# dabstick_eval_rev00.net
KiCad netlist of a schematic drawn in EAGLE
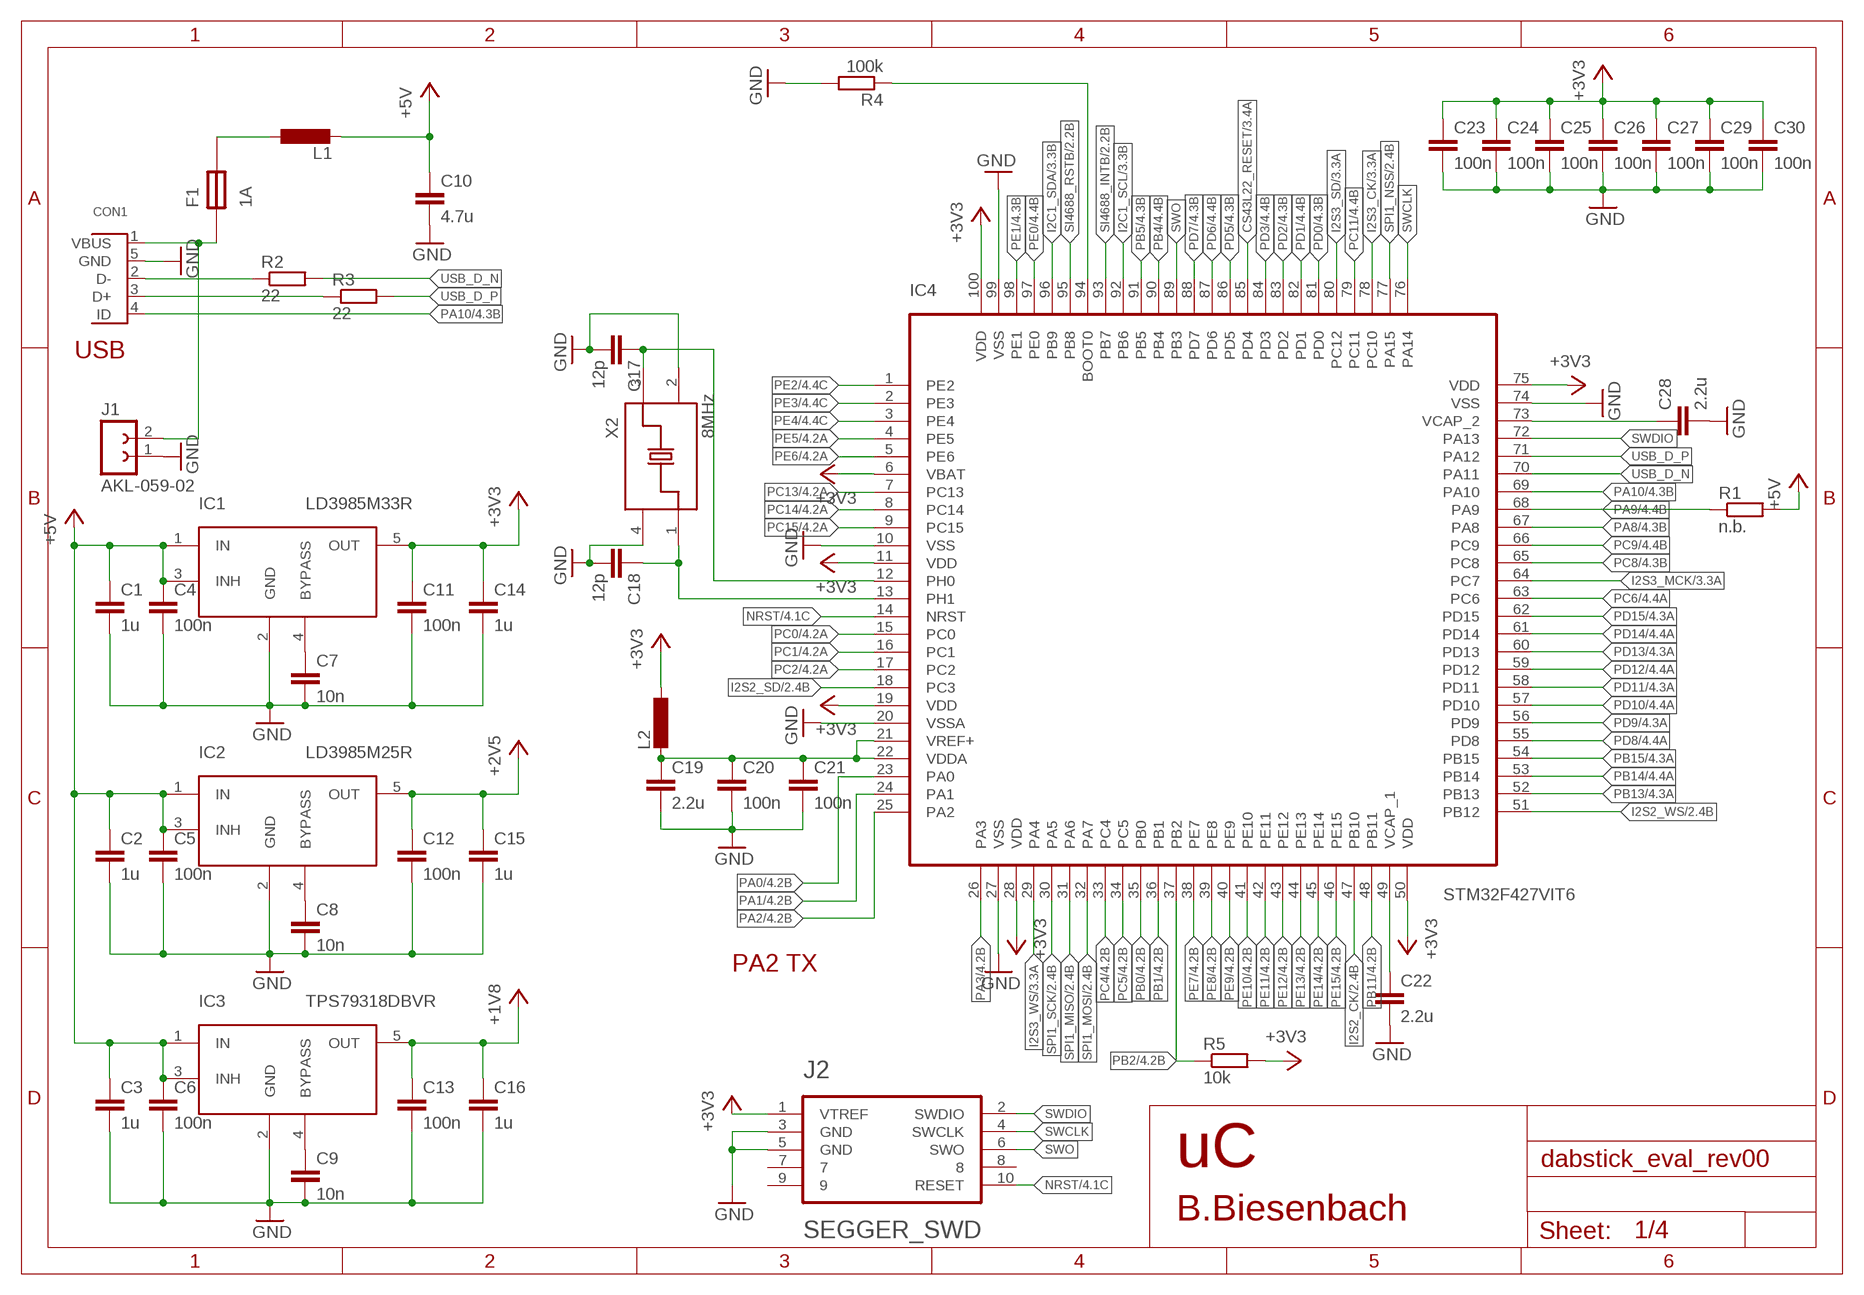
[diagram p0: schematic, sheet 1]
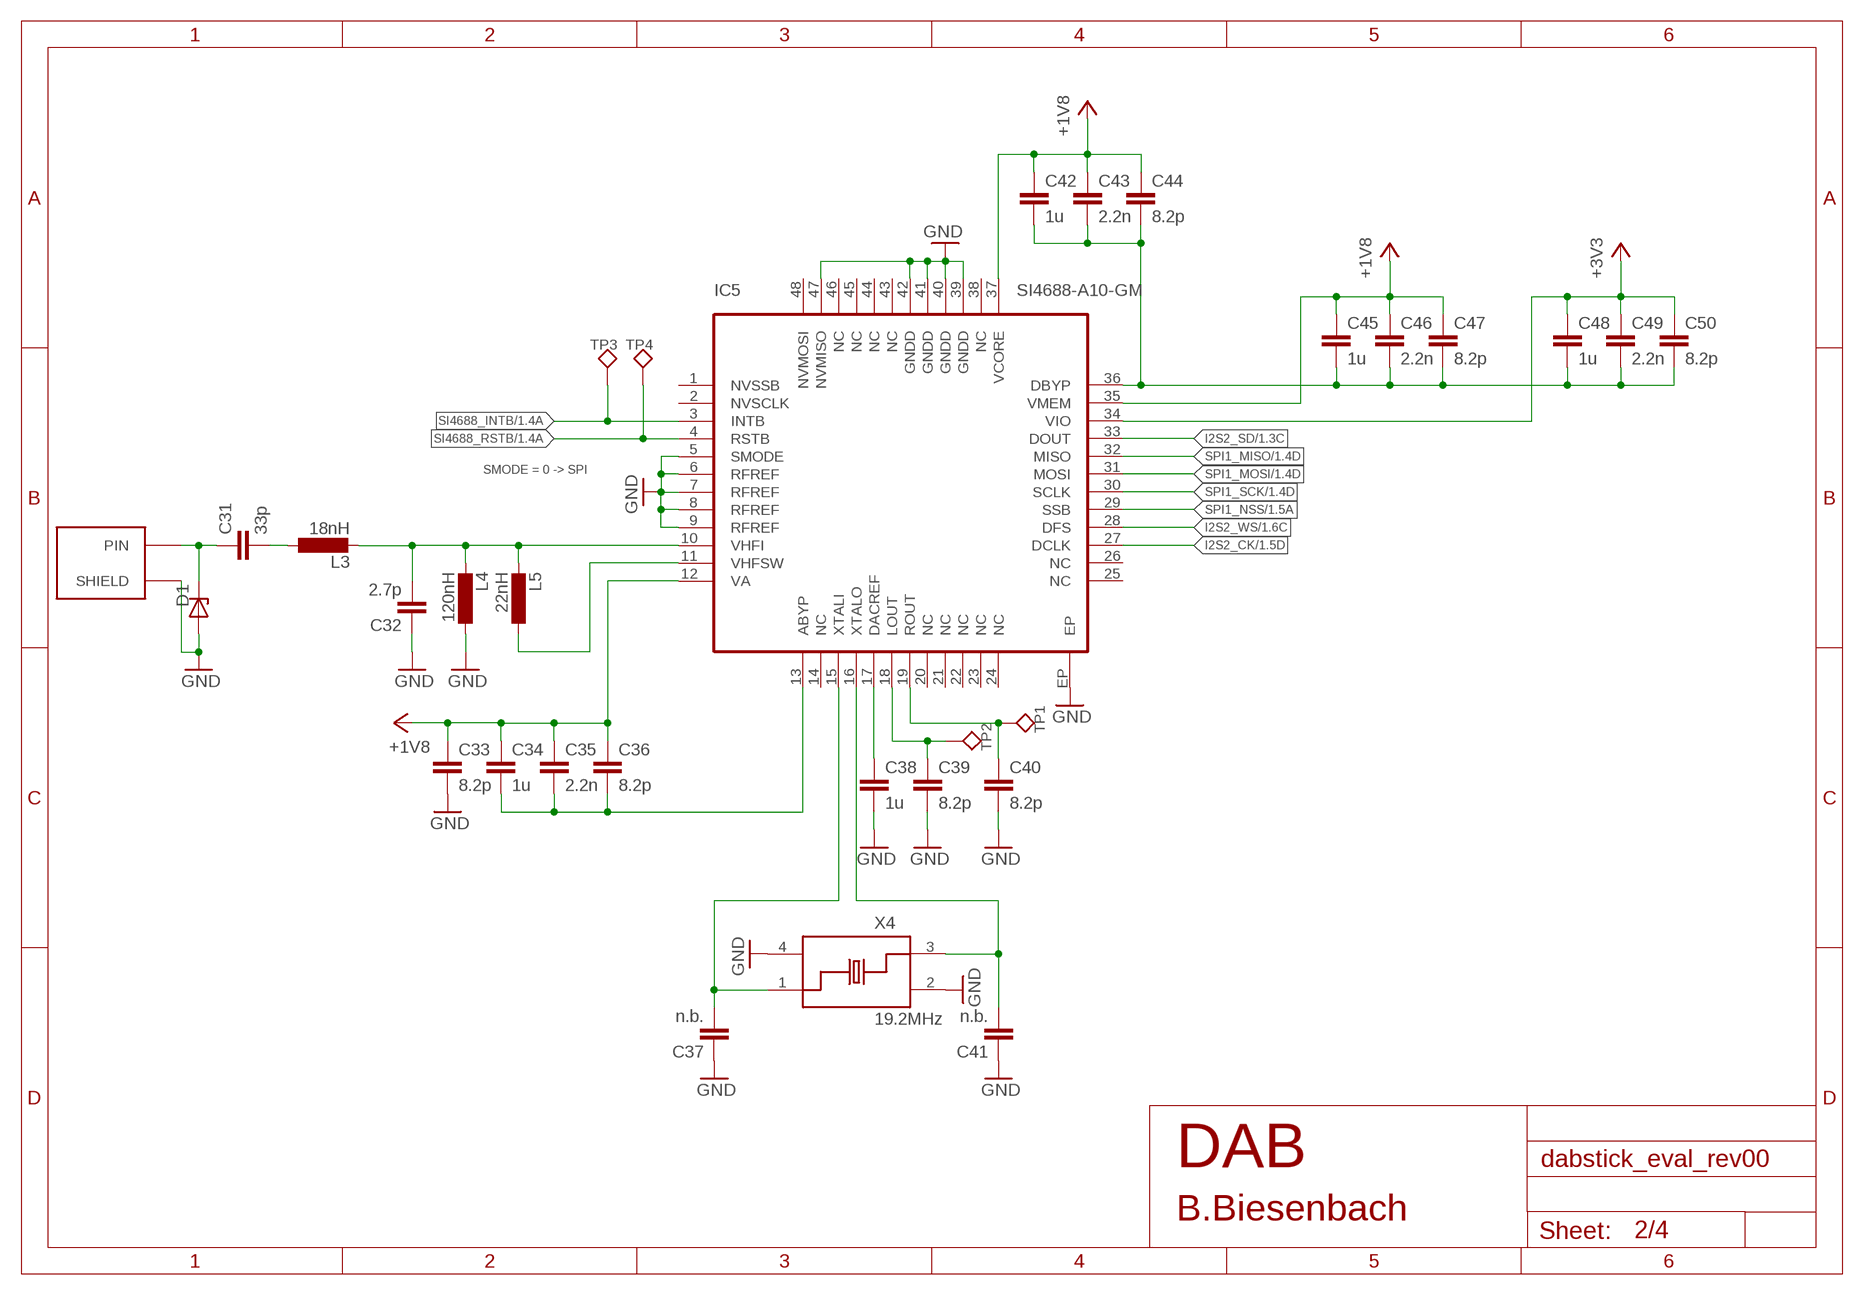
[diagram p1: schematic, sheet 2]
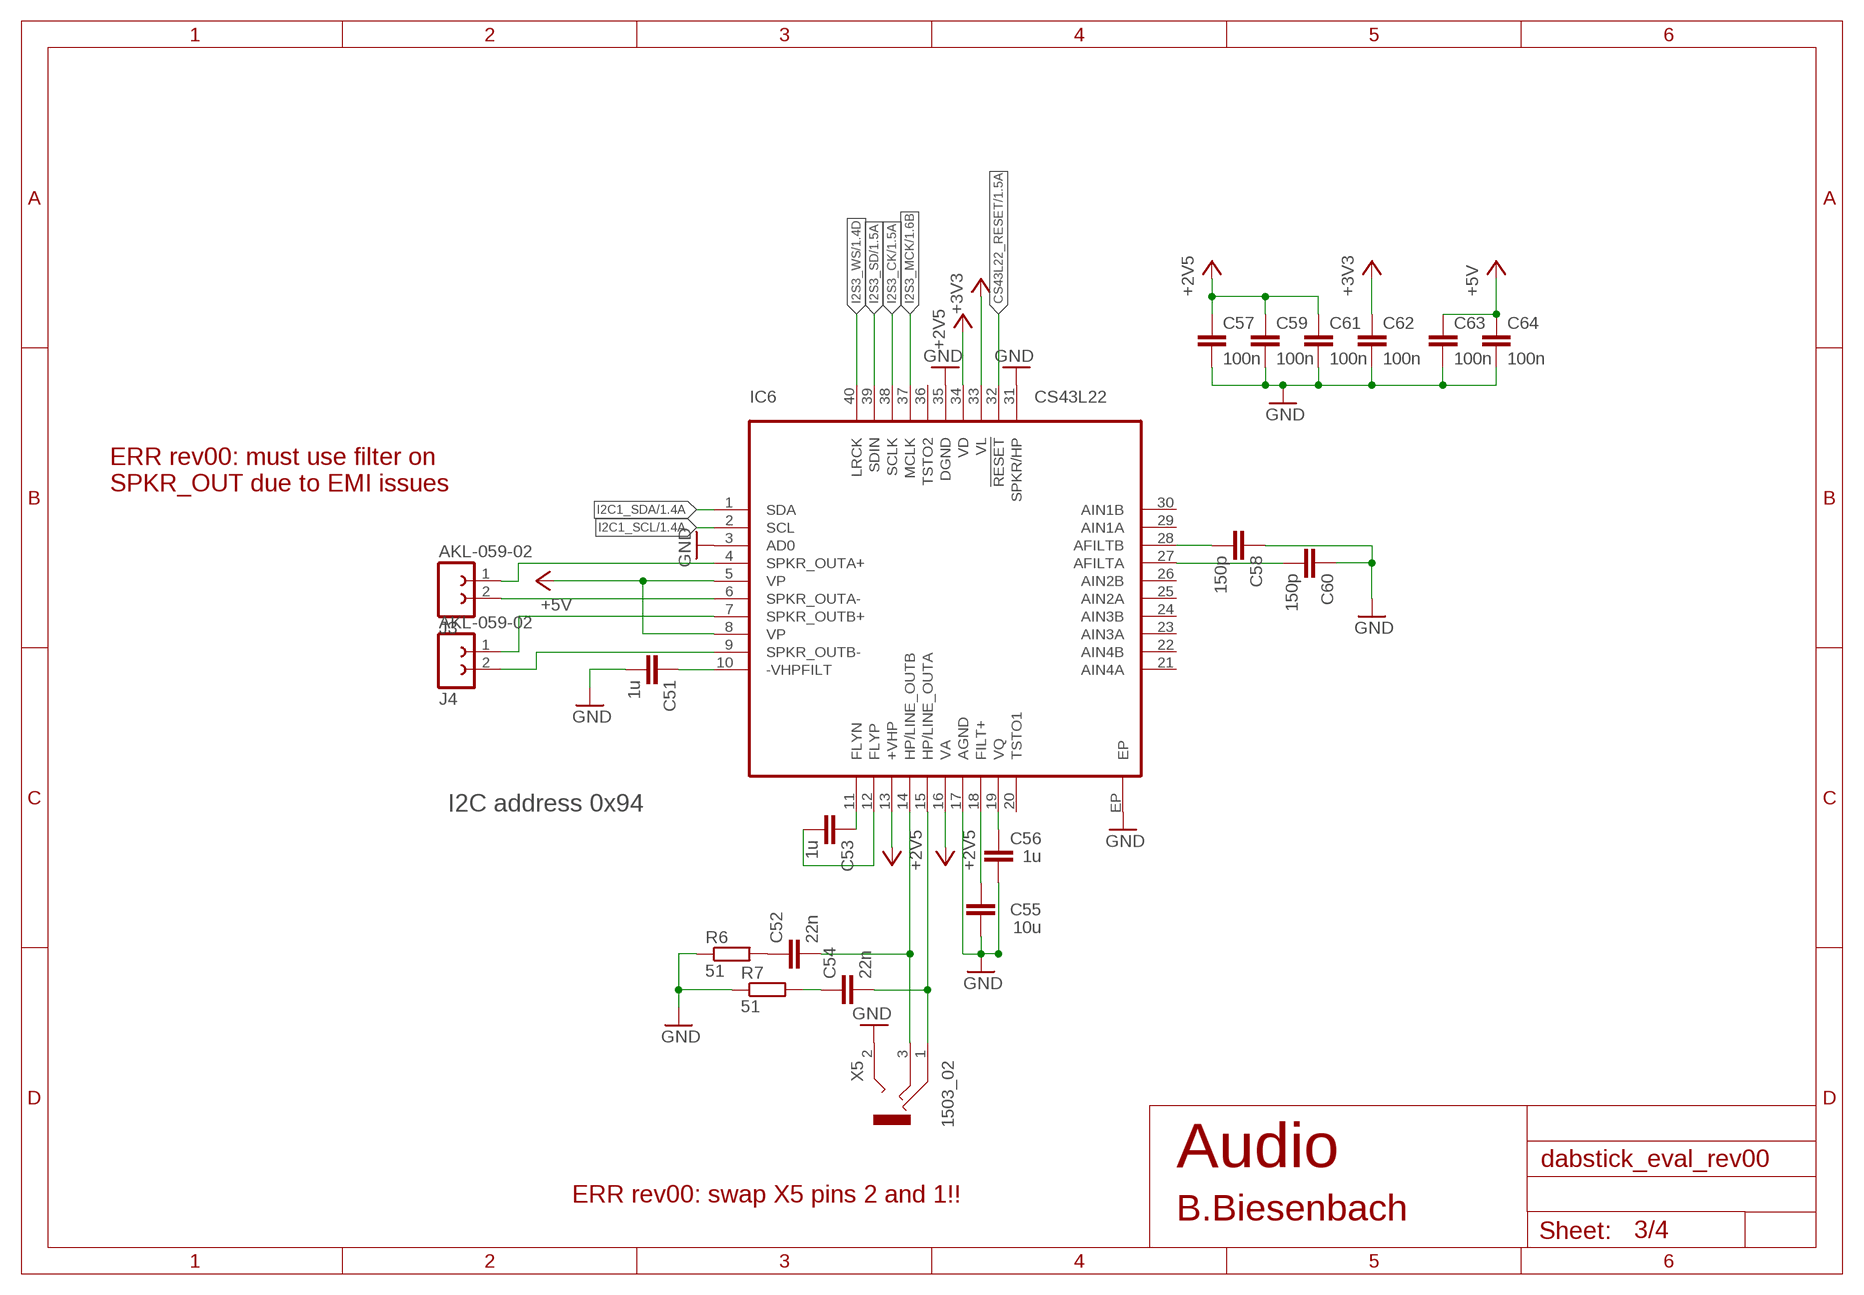
[diagram p2: schematic, sheet 3]
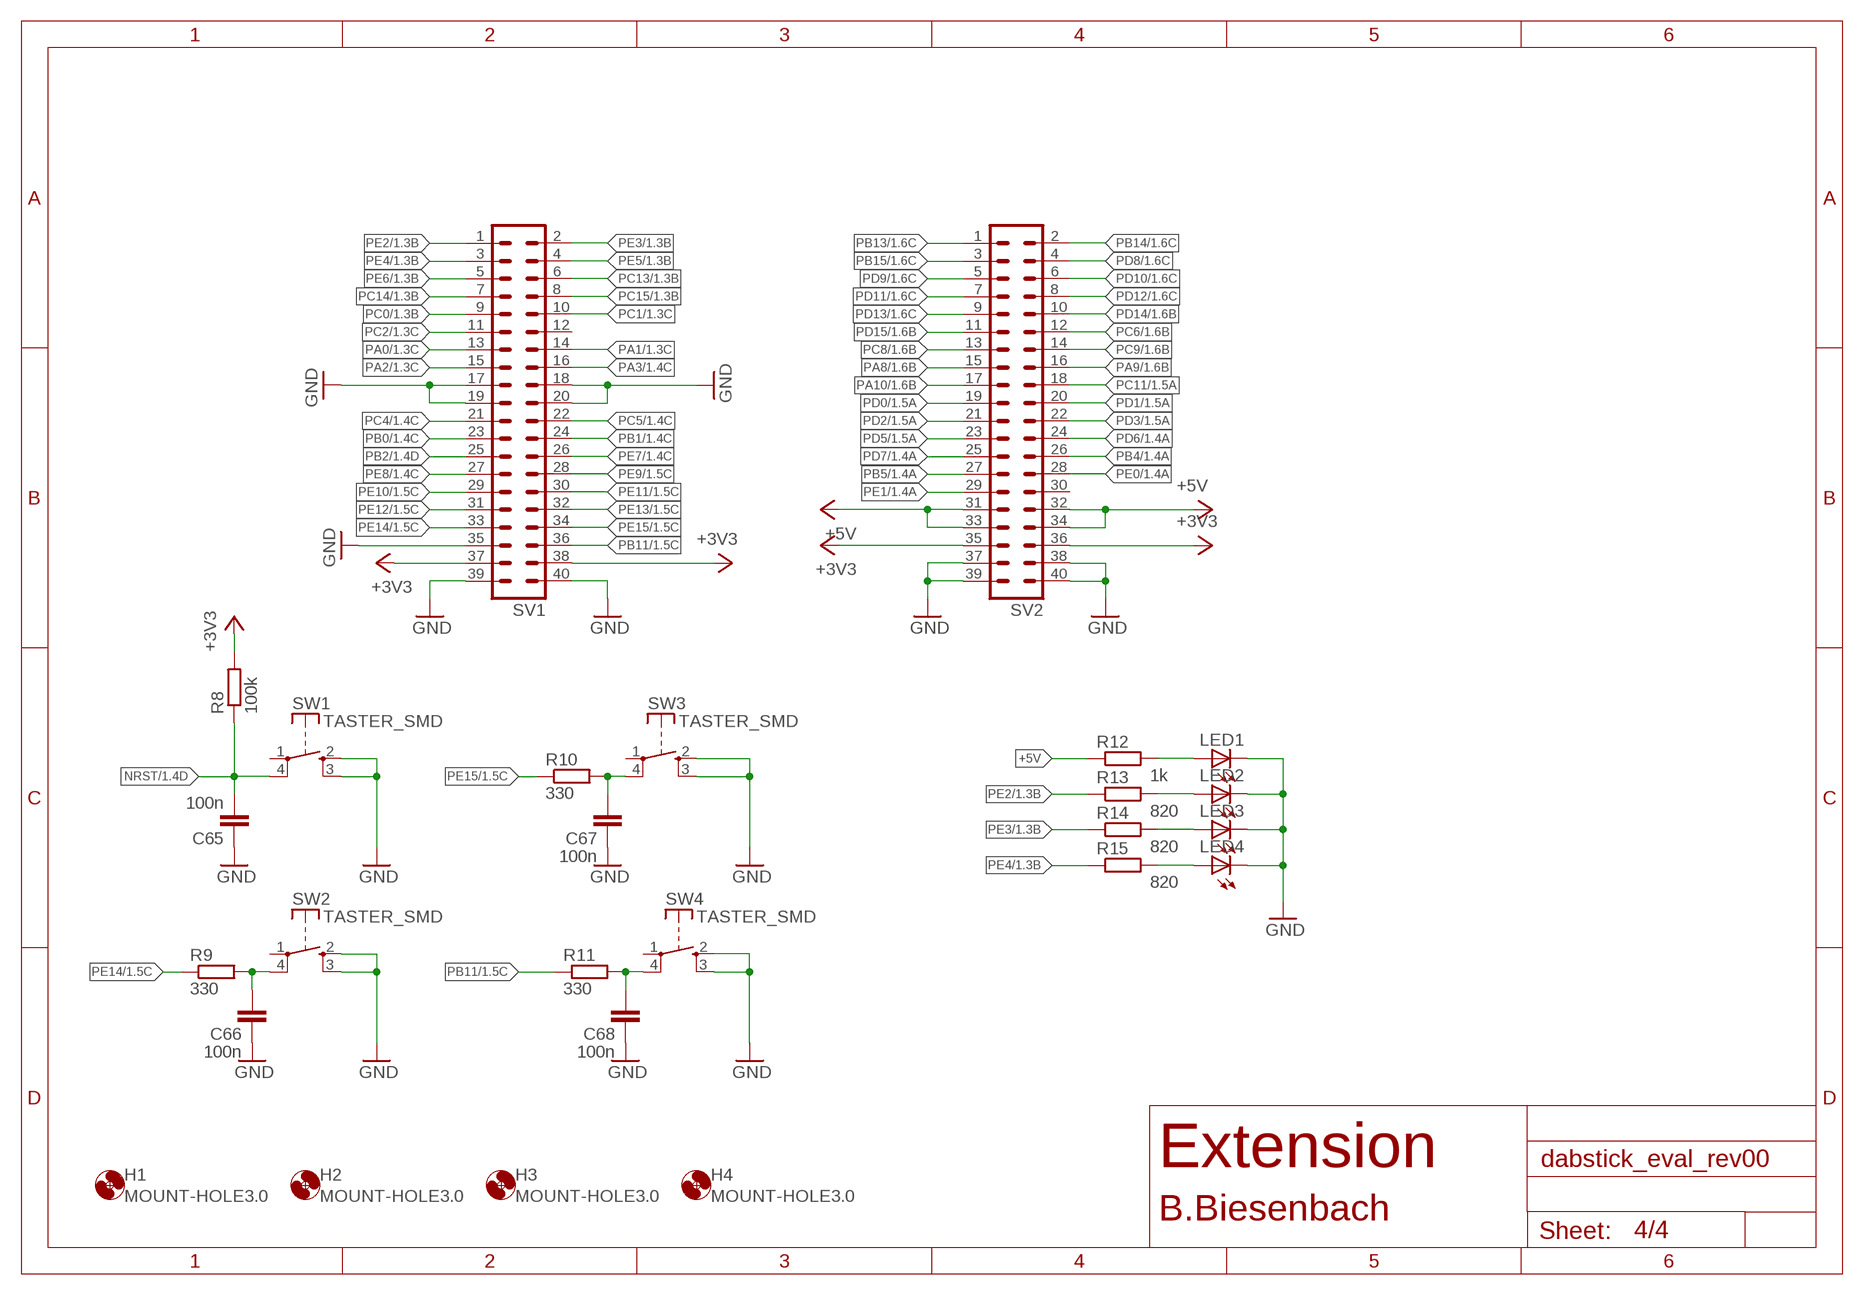
[diagram p3: schematic, sheet 4]

(export (version "E")
  (design (tool "Eeschema 10.0.6"))
  (components
    (comp (ref "C65")
      (value "100n")
      (footprint "eagle-import:SMD0603")
      (libsource (lib "eagle-import") (part "C0603"))
    )
    (comp (ref "C66")
      (value "100n")
      (footprint "eagle-import:SMD0603")
      (libsource (lib "eagle-import") (part "C0603"))
    )
    (comp (ref "C67")
      (value "100n")
      (footprint "eagle-import:SMD0603")
      (libsource (lib "eagle-import") (part "C0603"))
    )
    (comp (ref "C68")
      (value "100n")
      (footprint "eagle-import:SMD0603")
      (libsource (lib "eagle-import") (part "C0603"))
    )
    (comp (ref "H1")
      (value "MOUNT-HOLE3.0")
      (footprint "eagle-import:3,0")
      (libsource (lib "eagle-import") (part "MOUNT-HOLE3.0"))
    )
    (comp (ref "H2")
      (value "MOUNT-HOLE3.0")
      (footprint "eagle-import:3,0")
      (libsource (lib "eagle-import") (part "MOUNT-HOLE3.0"))
    )
    (comp (ref "H3")
      (value "MOUNT-HOLE3.0")
      (footprint "eagle-import:3,0")
      (libsource (lib "eagle-import") (part "MOUNT-HOLE3.0"))
    )
    (comp (ref "H4")
      (value "MOUNT-HOLE3.0")
      (footprint "eagle-import:3,0")
      (libsource (lib "eagle-import") (part "MOUNT-HOLE3.0"))
    )
    (comp (ref "LED1")
      (value "LEDCHIPLED_0603")
      (footprint "eagle-import:CHIPLED_0603")
      (libsource (lib "eagle-import") (part "LEDCHIPLED_0603"))
    )
    (comp (ref "LED2")
      (value "LEDCHIPLED_0603")
      (footprint "eagle-import:CHIPLED_0603")
      (libsource (lib "eagle-import") (part "LEDCHIPLED_0603"))
    )
    (comp (ref "LED3")
      (value "LEDCHIPLED_0603")
      (footprint "eagle-import:CHIPLED_0603")
      (libsource (lib "eagle-import") (part "LEDCHIPLED_0603"))
    )
    (comp (ref "LED4")
      (value "LEDCHIPLED_0603")
      (footprint "eagle-import:CHIPLED_0603")
      (libsource (lib "eagle-import") (part "LEDCHIPLED_0603"))
    )
    (comp (ref "R8")
      (value "100k")
      (footprint "eagle-import:SMD0603")
      (libsource (lib "eagle-import") (part "R0603"))
    )
    (comp (ref "R9")
      (value "330")
      (footprint "eagle-import:SMD0603")
      (libsource (lib "eagle-import") (part "R0603"))
    )
    (comp (ref "R10")
      (value "330")
      (footprint "eagle-import:SMD0603")
      (libsource (lib "eagle-import") (part "R0603"))
    )
    (comp (ref "R11")
      (value "330")
      (footprint "eagle-import:SMD0603")
      (libsource (lib "eagle-import") (part "R0603"))
    )
    (comp (ref "R12")
      (value "1k")
      (footprint "eagle-import:SMD0603")
      (libsource (lib "eagle-import") (part "R0603"))
    )
    (comp (ref "R13")
      (value "820")
      (footprint "eagle-import:SMD0603")
      (libsource (lib "eagle-import") (part "R0603"))
    )
    (comp (ref "R14")
      (value "820")
      (footprint "eagle-import:SMD0603")
      (libsource (lib "eagle-import") (part "R0603"))
    )
    (comp (ref "R15")
      (value "820")
      (footprint "eagle-import:SMD0603")
      (libsource (lib "eagle-import") (part "R0603"))
    )
    (comp (ref "SV1")
      (value "MA20-2")
      (footprint "eagle-import:MA20-2")
      (libsource (lib "eagle-import") (part "MA20-2"))
    )
    (comp (ref "SV2")
      (value "MA20-2")
      (footprint "eagle-import:MA20-2")
      (libsource (lib "eagle-import") (part "MA20-2"))
    )
    (comp (ref "SW1")
      (value "TASTER_SMD")
      (footprint "eagle-import:TASTER_SMD_ALPS")
      (libsource (lib "eagle-import") (part "TASTER_SMD"))
    )
    (comp (ref "SW2")
      (value "TASTER_SMD")
      (footprint "eagle-import:TASTER_SMD_ALPS")
      (libsource (lib "eagle-import") (part "TASTER_SMD"))
    )
    (comp (ref "SW3")
      (value "TASTER_SMD")
      (footprint "eagle-import:TASTER_SMD_ALPS")
      (libsource (lib "eagle-import") (part "TASTER_SMD"))
    )
    (comp (ref "SW4")
      (value "TASTER_SMD")
      (footprint "eagle-import:TASTER_SMD_ALPS")
      (libsource (lib "eagle-import") (part "TASTER_SMD"))
    )
    (comp (ref "C1")
      (value "1u")
      (footprint "eagle-import:SMD0603")
      (libsource (lib "eagle-import") (part "C0603"))
    )
    (comp (ref "C2")
      (value "1u")
      (footprint "eagle-import:SMD0603")
      (libsource (lib "eagle-import") (part "C0603"))
    )
    (comp (ref "C3")
      (value "1u")
      (footprint "eagle-import:SMD0603")
      (libsource (lib "eagle-import") (part "C0603"))
    )
    (comp (ref "C4")
      (value "100n")
      (footprint "eagle-import:SMD0603")
      (libsource (lib "eagle-import") (part "C0603"))
    )
    (comp (ref "C5")
      (value "100n")
      (footprint "eagle-import:SMD0603")
      (libsource (lib "eagle-import") (part "C0603"))
    )
    (comp (ref "C6")
      (value "100n")
      (footprint "eagle-import:SMD0603")
      (libsource (lib "eagle-import") (part "C0603"))
    )
    (comp (ref "C7")
      (value "10n")
      (footprint "eagle-import:SMD0603")
      (libsource (lib "eagle-import") (part "C0603"))
    )
    (comp (ref "C8")
      (value "10n")
      (footprint "eagle-import:SMD0603")
      (libsource (lib "eagle-import") (part "C0603"))
    )
    (comp (ref "C9")
      (value "10n")
      (footprint "eagle-import:SMD0603")
      (libsource (lib "eagle-import") (part "C0603"))
    )
    (comp (ref "C10")
      (value "4.7u")
      (footprint "eagle-import:0805")
      (libsource (lib "eagle-import") (part "C0805"))
    )
    (comp (ref "C11")
      (value "100n")
      (footprint "eagle-import:SMD0603")
      (libsource (lib "eagle-import") (part "C0603"))
    )
    (comp (ref "C12")
      (value "100n")
      (footprint "eagle-import:SMD0603")
      (libsource (lib "eagle-import") (part "C0603"))
    )
    (comp (ref "C13")
      (value "100n")
      (footprint "eagle-import:SMD0603")
      (libsource (lib "eagle-import") (part "C0603"))
    )
    (comp (ref "C14")
      (value "1u")
      (footprint "eagle-import:SMD0603")
      (libsource (lib "eagle-import") (part "C0603"))
    )
    (comp (ref "C15")
      (value "1u")
      (footprint "eagle-import:SMD0603")
      (libsource (lib "eagle-import") (part "C0603"))
    )
    (comp (ref "C16")
      (value "1u")
      (footprint "eagle-import:SMD0603")
      (libsource (lib "eagle-import") (part "C0603"))
    )
    (comp (ref "C17")
      (value "12p")
      (footprint "eagle-import:SMD0603")
      (libsource (lib "eagle-import") (part "C0603"))
    )
    (comp (ref "C18")
      (value "12p")
      (footprint "eagle-import:SMD0603")
      (libsource (lib "eagle-import") (part "C0603"))
    )
    (comp (ref "C19")
      (value "2.2u")
      (footprint "eagle-import:SMD0603")
      (libsource (lib "eagle-import") (part "C0603"))
    )
    (comp (ref "C20")
      (value "100n")
      (footprint "eagle-import:SMD0603")
      (libsource (lib "eagle-import") (part "C0603"))
    )
    (comp (ref "C21")
      (value "100n")
      (footprint "eagle-import:SMD0603")
      (libsource (lib "eagle-import") (part "C0603"))
    )
    (comp (ref "C22")
      (value "2.2u")
      (footprint "eagle-import:SMD0603")
      (libsource (lib "eagle-import") (part "C0603"))
    )
    (comp (ref "C23")
      (value "100n")
      (footprint "eagle-import:SMD0603")
      (libsource (lib "eagle-import") (part "C0603"))
    )
    (comp (ref "C24")
      (value "100n")
      (footprint "eagle-import:SMD0603")
      (libsource (lib "eagle-import") (part "C0603"))
    )
    (comp (ref "C25")
      (value "100n")
      (footprint "eagle-import:SMD0603")
      (libsource (lib "eagle-import") (part "C0603"))
    )
    (comp (ref "C26")
      (value "100n")
      (footprint "eagle-import:SMD0603")
      (libsource (lib "eagle-import") (part "C0603"))
    )
    (comp (ref "C27")
      (value "100n")
      (footprint "eagle-import:SMD0603")
      (libsource (lib "eagle-import") (part "C0603"))
    )
    (comp (ref "C28")
      (value "2.2u")
      (footprint "eagle-import:SMD0603")
      (libsource (lib "eagle-import") (part "C0603"))
    )
    (comp (ref "C29")
      (value "100n")
      (footprint "eagle-import:SMD0603")
      (libsource (lib "eagle-import") (part "C0603"))
    )
    (comp (ref "C30")
      (value "100n")
      (footprint "eagle-import:SMD0603")
      (libsource (lib "eagle-import") (part "C0603"))
    )
    (comp (ref "CON1")
      (value "USB")
      (footprint "eagle-import:USB-B-MICRO-SMT")
      (libsource (lib "eagle-import") (part "USB"))
    )
    (comp (ref "F1")
      (value "1A")
      (footprint "eagle-import:SMD_FUSE")
      (libsource (lib "eagle-import") (part "SMD_FUSE"))
    )
    (comp (ref "IC1")
      (value "LD3985M33R")
      (footprint "eagle-import:SOT23-5")
      (libsource (lib "eagle-import") (part "LD3985M33R"))
    )
    (comp (ref "IC2")
      (value "LD3985M25R")
      (footprint "eagle-import:SOT23-5")
      (libsource (lib "eagle-import") (part "LD3985M25R"))
    )
    (comp (ref "IC3")
      (value "TPS79318DBVR")
      (footprint "eagle-import:SOT23-5")
      (libsource (lib "eagle-import") (part "TPS79318DBVR"))
    )
    (comp (ref "IC4")
      (value "STM32F427VIT6")
      (footprint "eagle-import:LQFP100")
      (libsource (lib "eagle-import") (part "STM32F427VIT6"))
    )
    (comp (ref "J1")
      (value "AKL-059-02")
      (footprint "eagle-import:AKL-059-02")
      (libsource (lib "eagle-import") (part "AKL-059-02"))
    )
    (comp (ref "J2")
      (value "SEGGER_SWD")
      (footprint "eagle-import:HEADER_10_1.27")
      (libsource (lib "eagle-import") (part "SEGGER_SWD"))
    )
    (comp (ref "L1")
      (value "L08050805")
      (footprint "eagle-import:0805")
      (libsource (lib "eagle-import") (part "L08050805"))
    )
    (comp (ref "L2")
      (value "L0603")
      (footprint "eagle-import:SMD0603")
      (libsource (lib "eagle-import") (part "L0603"))
    )
    (comp (ref "R1")
      (value "n.b.")
      (footprint "eagle-import:SMD0603")
      (libsource (lib "eagle-import") (part "R0603"))
    )
    (comp (ref "R2")
      (value "22")
      (footprint "eagle-import:SMD0603")
      (libsource (lib "eagle-import") (part "R0603"))
    )
    (comp (ref "R3")
      (value "22")
      (footprint "eagle-import:SMD0603")
      (libsource (lib "eagle-import") (part "R0603"))
    )
    (comp (ref "R4")
      (value "100k")
      (footprint "eagle-import:SMD0603")
      (libsource (lib "eagle-import") (part "R0603"))
    )
    (comp (ref "R5")
      (value "10k")
      (footprint "eagle-import:SMD0603")
      (libsource (lib "eagle-import") (part "R0603"))
    )
    (comp (ref "X2")
      (value "8MHz")
      (footprint "eagle-import:XTAL_3.2X5")
      (libsource (lib "eagle-import") (part "XTAL_3.2X5"))
    )
    (comp (ref "C31")
      (value "33p")
      (footprint "eagle-import:SMD0402")
      (libsource (lib "eagle-import") (part "C0402"))
    )
    (comp (ref "C32")
      (value "2.7p")
      (footprint "eagle-import:SMD0402")
      (libsource (lib "eagle-import") (part "C0402"))
    )
    (comp (ref "C33")
      (value "8.2p")
      (footprint "eagle-import:SMD0603")
      (libsource (lib "eagle-import") (part "C0603"))
    )
    (comp (ref "C34")
      (value "1u")
      (footprint "eagle-import:SMD0603")
      (libsource (lib "eagle-import") (part "C0603"))
    )
    (comp (ref "C35")
      (value "2.2n")
      (footprint "eagle-import:SMD0603")
      (libsource (lib "eagle-import") (part "C0603"))
    )
    (comp (ref "C36")
      (value "8.2p")
      (footprint "eagle-import:SMD0603")
      (libsource (lib "eagle-import") (part "C0603"))
    )
    (comp (ref "C37")
      (value "n.b.")
      (footprint "eagle-import:SMD0402")
      (libsource (lib "eagle-import") (part "C0402"))
    )
    (comp (ref "C38")
      (value "1u")
      (footprint "eagle-import:SMD0603")
      (libsource (lib "eagle-import") (part "C0603"))
    )
    (comp (ref "C39")
      (value "8.2p")
      (footprint "eagle-import:SMD0603")
      (libsource (lib "eagle-import") (part "C0603"))
    )
    (comp (ref "C40")
      (value "8.2p")
      (footprint "eagle-import:SMD0603")
      (libsource (lib "eagle-import") (part "C0603"))
    )
    (comp (ref "C41")
      (value "n.b.")
      (footprint "eagle-import:SMD0402")
      (libsource (lib "eagle-import") (part "C0402"))
    )
    (comp (ref "C42")
      (value "1u")
      (footprint "eagle-import:SMD0603")
      (libsource (lib "eagle-import") (part "C0603"))
    )
    (comp (ref "C43")
      (value "2.2n")
      (footprint "eagle-import:SMD0603")
      (libsource (lib "eagle-import") (part "C0603"))
    )
    (comp (ref "C44")
      (value "8.2p")
      (footprint "eagle-import:SMD0603")
      (libsource (lib "eagle-import") (part "C0603"))
    )
    (comp (ref "C45")
      (value "1u")
      (footprint "eagle-import:SMD0603")
      (libsource (lib "eagle-import") (part "C0603"))
    )
    (comp (ref "C46")
      (value "2.2n")
      (footprint "eagle-import:SMD0603")
      (libsource (lib "eagle-import") (part "C0603"))
    )
    (comp (ref "C47")
      (value "8.2p")
      (footprint "eagle-import:SMD0603")
      (libsource (lib "eagle-import") (part "C0603"))
    )
    (comp (ref "C48")
      (value "1u")
      (footprint "eagle-import:SMD0603")
      (libsource (lib "eagle-import") (part "C0603"))
    )
    (comp (ref "C49")
      (value "2.2n")
      (footprint "eagle-import:SMD0603")
      (libsource (lib "eagle-import") (part "C0603"))
    )
    (comp (ref "C50")
      (value "8.2p")
      (footprint "eagle-import:SMD0603")
      (libsource (lib "eagle-import") (part "C0603"))
    )
    (comp (ref "D1")
      (value "ESD9L5.0")
      (footprint "eagle-import:SOD923")
      (libsource (lib "eagle-import") (part "ESD9L5.0"))
    )
    (comp (ref "IC5")
      (value "SI4688-A10-GM")
      (footprint "eagle-import:QFN48")
      (libsource (lib "eagle-import") (part "SI4688-A10-GM"))
    )
    (comp (ref "L3")
      (value "18nH")
      (footprint "eagle-import:SMD0402")
      (libsource (lib "eagle-import") (part "L0402"))
    )
    (comp (ref "L4")
      (value "120nH")
      (footprint "eagle-import:SMD0402")
      (libsource (lib "eagle-import") (part "L0402"))
    )
    (comp (ref "L5")
      (value "22nH")
      (footprint "eagle-import:SMD0402")
      (libsource (lib "eagle-import") (part "L0402"))
    )
    (comp (ref "TP1")
      (value "TP-2-MM")
      (footprint "eagle-import:TP-2-MM")
      (libsource (lib "eagle-import") (part "TP-2-MM"))
    )
    (comp (ref "TP2")
      (value "TP-2-MM")
      (footprint "eagle-import:TP-2-MM")
      (libsource (lib "eagle-import") (part "TP-2-MM"))
    )
    (comp (ref "TP3")
      (value "TP-1-MM")
      (footprint "eagle-import:TP-1-MM")
      (libsource (lib "eagle-import") (part "TP-1-MM"))
    )
    (comp (ref "TP4")
      (value "TP-1-MM")
      (footprint "eagle-import:TP-1-MM")
      (libsource (lib "eagle-import") (part "TP-1-MM"))
    )
    (comp (ref "X3")
      (value "SMA_LP_1.57MM")
      (footprint "eagle-import:SMA_LP_1.57MM")
      (libsource (lib "eagle-import") (part "SMA_LP_1.57MM"))
    )
    (comp (ref "X4")
      (value "19.2MHz")
      (footprint "eagle-import:XTAL_3.2X2.5")
      (libsource (lib "eagle-import") (part "XTAL_3.2X2.5"))
    )
    (comp (ref "C51")
      (value "1u")
      (footprint "eagle-import:SMD0603")
      (libsource (lib "eagle-import") (part "C0603"))
    )
    (comp (ref "C52")
      (value "22n")
      (footprint "eagle-import:SMD0603")
      (libsource (lib "eagle-import") (part "C0603"))
    )
    (comp (ref "C53")
      (value "1u")
      (footprint "eagle-import:SMD0603")
      (libsource (lib "eagle-import") (part "C0603"))
    )
    (comp (ref "C54")
      (value "22n")
      (footprint "eagle-import:SMD0603")
      (libsource (lib "eagle-import") (part "C0603"))
    )
    (comp (ref "C55")
      (value "10u")
      (footprint "eagle-import:SMD0603")
      (libsource (lib "eagle-import") (part "C0603"))
    )
    (comp (ref "C56")
      (value "1u")
      (footprint "eagle-import:SMD0603")
      (libsource (lib "eagle-import") (part "C0603"))
    )
    (comp (ref "C57")
      (value "100n")
      (footprint "eagle-import:SMD0603")
      (libsource (lib "eagle-import") (part "C0603"))
    )
    (comp (ref "C58")
      (value "150p")
      (footprint "eagle-import:SMD0603")
      (libsource (lib "eagle-import") (part "C0603"))
    )
    (comp (ref "C59")
      (value "100n")
      (footprint "eagle-import:SMD0603")
      (libsource (lib "eagle-import") (part "C0603"))
    )
    (comp (ref "C60")
      (value "150p")
      (footprint "eagle-import:SMD0603")
      (libsource (lib "eagle-import") (part "C0603"))
    )
    (comp (ref "C61")
      (value "100n")
      (footprint "eagle-import:SMD0603")
      (libsource (lib "eagle-import") (part "C0603"))
    )
    (comp (ref "C62")
      (value "100n")
      (footprint "eagle-import:SMD0603")
      (libsource (lib "eagle-import") (part "C0603"))
    )
    (comp (ref "C63")
      (value "100n")
      (footprint "eagle-import:SMD0603")
      (libsource (lib "eagle-import") (part "C0603"))
    )
    (comp (ref "C64")
      (value "100n")
      (footprint "eagle-import:SMD0603")
      (libsource (lib "eagle-import") (part "C0603"))
    )
    (comp (ref "IC6")
      (value "CS43L22")
      (footprint "eagle-import:QFN40")
      (libsource (lib "eagle-import") (part "CS43L22"))
    )
    (comp (ref "J3")
      (value "AKL-059-02")
      (footprint "eagle-import:AKL-059-02")
      (libsource (lib "eagle-import") (part "AKL-059-02"))
    )
    (comp (ref "J4")
      (value "AKL-059-02")
      (footprint "eagle-import:AKL-059-02")
      (libsource (lib "eagle-import") (part "AKL-059-02"))
    )
    (comp (ref "R6")
      (value "51")
      (footprint "eagle-import:SMD0603")
      (libsource (lib "eagle-import") (part "R0603"))
    )
    (comp (ref "R7")
      (value "51")
      (footprint "eagle-import:SMD0603")
      (libsource (lib "eagle-import") (part "R0603"))
    )
    (comp (ref "X5")
      (value "1503_02")
      (footprint "eagle-import:1503_02")
      (libsource (lib "eagle-import") (part "1503_02"))
    )
  )
  (nets
    (net (code "1") (name "+1V8") (class "Default")
      (node (ref "C13") (pin "1") (pinfunction "1_1") (pintype "passive"))
      (node (ref "C16") (pin "1") (pinfunction "1_1") (pintype "passive"))
      (node (ref "C33") (pin "1") (pinfunction "1_1") (pintype "passive"))
      (node (ref "C34") (pin "1") (pinfunction "1_1") (pintype "passive"))
      (node (ref "C35") (pin "1") (pinfunction "1_1") (pintype "passive"))
      (node (ref "C36") (pin "1") (pinfunction "1_1") (pintype "passive"))
      (node (ref "C42") (pin "1") (pinfunction "1_1") (pintype "passive"))
      (node (ref "C43") (pin "1") (pinfunction "1_1") (pintype "passive"))
      (node (ref "C44") (pin "1") (pinfunction "1_1") (pintype "passive"))
      (node (ref "C45") (pin "1") (pinfunction "1_1") (pintype "passive"))
      (node (ref "C46") (pin "1") (pinfunction "1_1") (pintype "passive"))
      (node (ref "C47") (pin "1") (pinfunction "1_1") (pintype "passive"))
      (node (ref "IC3") (pin "5") (pinfunction "OUT_5") (pintype "power_in"))
      (node (ref "IC5") (pin "12") (pinfunction "VA_12") (pintype "power_in"))
      (node (ref "IC5") (pin "35") (pinfunction "VMEM_35") (pintype "power_in"))
      (node (ref "IC5") (pin "37") (pinfunction "VCORE_37") (pintype "power_in"))
    )
    (net (code "2") (name "+2V5") (class "Default")
      (node (ref "C12") (pin "1") (pinfunction "1_1") (pintype "passive"))
      (node (ref "C15") (pin "1") (pinfunction "1_1") (pintype "passive"))
      (node (ref "C57") (pin "1") (pinfunction "1_1") (pintype "passive"))
      (node (ref "C59") (pin "1") (pinfunction "1_1") (pintype "passive"))
      (node (ref "C61") (pin "1") (pinfunction "1_1") (pintype "passive"))
      (node (ref "IC2") (pin "5") (pinfunction "OUT_5") (pintype "power_in"))
      (node (ref "IC6") (pin "13") (pinfunction "+VHP_13") (pintype "power_in"))
      (node (ref "IC6") (pin "16") (pinfunction "VA_16") (pintype "power_in"))
      (node (ref "IC6") (pin "34") (pinfunction "VD_34") (pintype "power_in"))
    )
    (net (code "3") (name "+3V3") (class "Default")
      (node (ref "C11") (pin "1") (pinfunction "1_1") (pintype "passive"))
      (node (ref "C14") (pin "1") (pinfunction "1_1") (pintype "passive"))
      (node (ref "C23") (pin "1") (pinfunction "1_1") (pintype "passive"))
      (node (ref "C24") (pin "1") (pinfunction "1_1") (pintype "passive"))
      (node (ref "C25") (pin "1") (pinfunction "1_1") (pintype "passive"))
      (node (ref "C26") (pin "1") (pinfunction "1_1") (pintype "passive"))
      (node (ref "C27") (pin "1") (pinfunction "1_1") (pintype "passive"))
      (node (ref "C29") (pin "1") (pinfunction "1_1") (pintype "passive"))
      (node (ref "C30") (pin "1") (pinfunction "1_1") (pintype "passive"))
      (node (ref "C48") (pin "1") (pinfunction "1_1") (pintype "passive"))
      (node (ref "C49") (pin "1") (pinfunction "1_1") (pintype "passive"))
      (node (ref "C50") (pin "1") (pinfunction "1_1") (pintype "passive"))
      (node (ref "C62") (pin "1") (pinfunction "1_1") (pintype "passive"))
      (node (ref "IC1") (pin "5") (pinfunction "OUT_5") (pintype "power_in"))
      (node (ref "IC4") (pin "100") (pinfunction "VDD_100") (pintype "power_in"))
      (node (ref "IC4") (pin "11") (pinfunction "VDD_11") (pintype "power_in"))
      (node (ref "IC4") (pin "19") (pinfunction "VDD_19") (pintype "power_in"))
      (node (ref "IC4") (pin "28") (pinfunction "VDD_28") (pintype "power_in"))
      (node (ref "IC4") (pin "50") (pinfunction "VDD_50") (pintype "power_in"))
      (node (ref "IC4") (pin "6") (pinfunction "VBAT_6") (pintype "bidirectional"))
      (node (ref "IC4") (pin "75") (pinfunction "VDD_75") (pintype "power_in"))
      (node (ref "IC5") (pin "34") (pinfunction "VIO_34") (pintype "power_in"))
      (node (ref "IC6") (pin "33") (pinfunction "VL_33") (pintype "power_in"))
      (node (ref "J2") (pin "1") (pinfunction "VTREF_1") (pintype "power_in"))
      (node (ref "L2") (pin "1") (pinfunction "1_1") (pintype "passive"))
      (node (ref "R5") (pin "2") (pinfunction "2_2") (pintype "passive"))
      (node (ref "R8") (pin "2") (pinfunction "2_2") (pintype "passive"))
      (node (ref "SV1") (pin "37") (pinfunction "37_37") (pintype "passive"))
      (node (ref "SV1") (pin "38") (pinfunction "38_38") (pintype "passive"))
      (node (ref "SV2") (pin "35") (pinfunction "35_35") (pintype "passive"))
      (node (ref "SV2") (pin "36") (pinfunction "36_36") (pintype "passive"))
    )
    (net (code "4") (name "+5V") (class "Default")
      (node (ref "C1") (pin "1") (pinfunction "1_1") (pintype "passive"))
      (node (ref "C10") (pin "1") (pinfunction "1_1") (pintype "passive"))
      (node (ref "C2") (pin "1") (pinfunction "1_1") (pintype "passive"))
      (node (ref "C3") (pin "1") (pinfunction "1_1") (pintype "passive"))
      (node (ref "C4") (pin "1") (pinfunction "1_1") (pintype "passive"))
      (node (ref "C5") (pin "1") (pinfunction "1_1") (pintype "passive"))
      (node (ref "C6") (pin "1") (pinfunction "1_1") (pintype "passive"))
      (node (ref "C63") (pin "1") (pinfunction "1_1") (pintype "passive"))
      (node (ref "C64") (pin "1") (pinfunction "1_1") (pintype "passive"))
      (node (ref "IC1") (pin "1") (pinfunction "IN_1") (pintype "power_in"))
      (node (ref "IC1") (pin "3") (pinfunction "INH_3") (pintype "input"))
      (node (ref "IC2") (pin "1") (pinfunction "IN_1") (pintype "power_in"))
      (node (ref "IC2") (pin "3") (pinfunction "INH_3") (pintype "input"))
      (node (ref "IC3") (pin "1") (pinfunction "IN_1") (pintype "power_in"))
      (node (ref "IC3") (pin "3") (pinfunction "INH_3") (pintype "input"))
      (node (ref "IC6") (pin "5") (pinfunction "VP_5") (pintype "power_in"))
      (node (ref "IC6") (pin "8") (pinfunction "VP_8") (pintype "power_in"))
      (node (ref "L1") (pin "2") (pinfunction "2_2") (pintype "passive"))
      (node (ref "R1") (pin "2") (pinfunction "2_2") (pintype "passive"))
      (node (ref "R12") (pin "1") (pinfunction "1_1") (pintype "passive"))
      (node (ref "SV2") (pin "31") (pinfunction "31_31") (pintype "passive"))
      (node (ref "SV2") (pin "32") (pinfunction "32_32") (pintype "passive"))
      (node (ref "SV2") (pin "33") (pinfunction "33_33") (pintype "passive"))
      (node (ref "SV2") (pin "34") (pinfunction "34_34") (pintype "passive"))
    )
    (net (code "5") (name "CS43L22_RESET") (class "Default")
      (node (ref "IC4") (pin "85") (pinfunction "PD4_85") (pintype "bidirectional"))
      (node (ref "IC6") (pin "32") (pinfunction "~{RESET}_32") (pintype "input"))
    )
    (net (code "6") (name "GND") (class "Default")
      (node (ref "C1") (pin "2") (pinfunction "2_2") (pintype "passive"))
      (node (ref "C10") (pin "2") (pinfunction "2_2") (pintype "passive"))
      (node (ref "C11") (pin "2") (pinfunction "2_2") (pintype "passive"))
      (node (ref "C12") (pin "2") (pinfunction "2_2") (pintype "passive"))
      (node (ref "C13") (pin "2") (pinfunction "2_2") (pintype "passive"))
      (node (ref "C14") (pin "2") (pinfunction "2_2") (pintype "passive"))
      (node (ref "C15") (pin "2") (pinfunction "2_2") (pintype "passive"))
      (node (ref "C16") (pin "2") (pinfunction "2_2") (pintype "passive"))
      (node (ref "C17") (pin "2") (pinfunction "2_2") (pintype "passive"))
      (node (ref "C18") (pin "2") (pinfunction "2_2") (pintype "passive"))
      (node (ref "C19") (pin "2") (pinfunction "2_2") (pintype "passive"))
      (node (ref "C2") (pin "2") (pinfunction "2_2") (pintype "passive"))
      (node (ref "C20") (pin "2") (pinfunction "2_2") (pintype "passive"))
      (node (ref "C21") (pin "2") (pinfunction "2_2") (pintype "passive"))
      (node (ref "C22") (pin "2") (pinfunction "2_2") (pintype "passive"))
      (node (ref "C23") (pin "2") (pinfunction "2_2") (pintype "passive"))
      (node (ref "C24") (pin "2") (pinfunction "2_2") (pintype "passive"))
      (node (ref "C25") (pin "2") (pinfunction "2_2") (pintype "passive"))
      (node (ref "C26") (pin "2") (pinfunction "2_2") (pintype "passive"))
      (node (ref "C27") (pin "2") (pinfunction "2_2") (pintype "passive"))
      (node (ref "C28") (pin "2") (pinfunction "2_2") (pintype "passive"))
      (node (ref "C29") (pin "2") (pinfunction "2_2") (pintype "passive"))
      (node (ref "C3") (pin "2") (pinfunction "2_2") (pintype "passive"))
      (node (ref "C30") (pin "2") (pinfunction "2_2") (pintype "passive"))
      (node (ref "C32") (pin "1") (pinfunction "1_1") (pintype "passive"))
      (node (ref "C33") (pin "2") (pinfunction "2_2") (pintype "passive"))
      (node (ref "C37") (pin "1") (pinfunction "1_1") (pintype "passive"))
      (node (ref "C38") (pin "2") (pinfunction "2_2") (pintype "passive"))
      (node (ref "C39") (pin "2") (pinfunction "2_2") (pintype "passive"))
      (node (ref "C4") (pin "2") (pinfunction "2_2") (pintype "passive"))
      (node (ref "C40") (pin "2") (pinfunction "2_2") (pintype "passive"))
      (node (ref "C41") (pin "1") (pinfunction "1_1") (pintype "passive"))
      (node (ref "C5") (pin "2") (pinfunction "2_2") (pintype "passive"))
      (node (ref "C51") (pin "2") (pinfunction "2_2") (pintype "passive"))
      (node (ref "C55") (pin "1") (pinfunction "1_1") (pintype "passive"))
      (node (ref "C56") (pin "1") (pinfunction "1_1") (pintype "passive"))
      (node (ref "C57") (pin "2") (pinfunction "2_2") (pintype "passive"))
      (node (ref "C58") (pin "1") (pinfunction "1_1") (pintype "passive"))
      (node (ref "C59") (pin "2") (pinfunction "2_2") (pintype "passive"))
      (node (ref "C6") (pin "2") (pinfunction "2_2") (pintype "passive"))
      (node (ref "C60") (pin "1") (pinfunction "1_1") (pintype "passive"))
      (node (ref "C61") (pin "2") (pinfunction "2_2") (pintype "passive"))
      (node (ref "C62") (pin "2") (pinfunction "2_2") (pintype "passive"))
      (node (ref "C63") (pin "2") (pinfunction "2_2") (pintype "passive"))
      (node (ref "C64") (pin "2") (pinfunction "2_2") (pintype "passive"))
      (node (ref "C65") (pin "1") (pinfunction "1_1") (pintype "passive"))
      (node (ref "C66") (pin "1") (pinfunction "1_1") (pintype "passive"))
      (node (ref "C67") (pin "1") (pinfunction "1_1") (pintype "passive"))
      (node (ref "C68") (pin "1") (pinfunction "1_1") (pintype "passive"))
      (node (ref "C7") (pin "2") (pinfunction "2_2") (pintype "passive"))
      (node (ref "C8") (pin "2") (pinfunction "2_2") (pintype "passive"))
      (node (ref "C9") (pin "2") (pinfunction "2_2") (pintype "passive"))
      (node (ref "CON1") (pin "5") (pinfunction "GND_5") (pintype "bidirectional"))
      (node (ref "D1") (pin "A") (pinfunction "A_A") (pintype "passive"))
      (node (ref "IC1") (pin "2") (pinfunction "GND_2") (pintype "power_in"))
      (node (ref "IC2") (pin "2") (pinfunction "GND_2") (pintype "power_in"))
      (node (ref "IC3") (pin "2") (pinfunction "GND_2") (pintype "power_in"))
      (node (ref "IC4") (pin "10") (pinfunction "VSS_10") (pintype "power_in"))
      (node (ref "IC4") (pin "20") (pinfunction "VSSA_20") (pintype "power_in"))
      (node (ref "IC4") (pin "27") (pinfunction "VSS_27") (pintype "power_in"))
      (node (ref "IC4") (pin "74") (pinfunction "VSS_74") (pintype "power_in"))
      (node (ref "IC4") (pin "99") (pinfunction "VSS_99") (pintype "power_in"))
      (node (ref "IC5") (pin "39") (pinfunction "GNDD_39") (pintype "power_in"))
      (node (ref "IC5") (pin "40") (pinfunction "GNDD_40") (pintype "power_in"))
      (node (ref "IC5") (pin "41") (pinfunction "GNDD_41") (pintype "power_in"))
      (node (ref "IC5") (pin "42") (pinfunction "GNDD_42") (pintype "power_in"))
      (node (ref "IC5") (pin "47") (pinfunction "NVMISO_47") (pintype "input"))
      (node (ref "IC5") (pin "5") (pinfunction "SMODE_5") (pintype "input"))
      (node (ref "IC5") (pin "6") (pinfunction "RFREF_6") (pintype "power_in"))
      (node (ref "IC5") (pin "7") (pinfunction "RFREF_7") (pintype "power_in"))
      (node (ref "IC5") (pin "8") (pinfunction "RFREF_8") (pintype "power_in"))
      (node (ref "IC5") (pin "9") (pinfunction "RFREF_9") (pintype "power_in"))
      (node (ref "IC5") (pin "EP") (pinfunction "EP_EP") (pintype "bidirectional"))
      (node (ref "IC6") (pin "17") (pinfunction "AGND_17") (pintype "power_in"))
      (node (ref "IC6") (pin "3") (pinfunction "AD0_3") (pintype "bidirectional"))
      (node (ref "IC6") (pin "31") (pinfunction "SPKR/HP_31") (pintype "input"))
      (node (ref "IC6") (pin "35") (pinfunction "DGND_35") (pintype "power_in"))
      (node (ref "IC6") (pin "EP") (pinfunction "EP_EP") (pintype "bidirectional"))
      (node (ref "J1") (pin "1") (pinfunction "1_1") (pintype "passive"))
      (node (ref "J2") (pin "3") (pinfunction "GND_3") (pintype "bidirectional"))
      (node (ref "J2") (pin "5") (pinfunction "GND_5") (pintype "bidirectional"))
      (node (ref "L4") (pin "1") (pinfunction "1_1") (pintype "passive"))
      (node (ref "LED1") (pin "C") (pinfunction "C_C") (pintype "passive"))
      (node (ref "LED2") (pin "C") (pinfunction "C_C") (pintype "passive"))
      (node (ref "LED3") (pin "C") (pinfunction "C_C") (pintype "passive"))
      (node (ref "LED4") (pin "C") (pinfunction "C_C") (pintype "passive"))
      (node (ref "R4") (pin "2") (pinfunction "2_2") (pintype "passive"))
      (node (ref "R6") (pin "1") (pinfunction "1_1") (pintype "passive"))
      (node (ref "R7") (pin "1") (pinfunction "1_1") (pintype "passive"))
      (node (ref "SV1") (pin "17") (pinfunction "17_17") (pintype "passive"))
      (node (ref "SV1") (pin "18") (pinfunction "18_18") (pintype "passive"))
      (node (ref "SV1") (pin "19") (pinfunction "19_19") (pintype "passive"))
      (node (ref "SV1") (pin "20") (pinfunction "20_20") (pintype "passive"))
      (node (ref "SV1") (pin "35") (pinfunction "35_35") (pintype "passive"))
      (node (ref "SV1") (pin "39") (pinfunction "39_39") (pintype "passive"))
      (node (ref "SV1") (pin "40") (pinfunction "40_40") (pintype "passive"))
      (node (ref "SV2") (pin "37") (pinfunction "37_37") (pintype "passive"))
      (node (ref "SV2") (pin "38") (pinfunction "38_38") (pintype "passive"))
      (node (ref "SV2") (pin "39") (pinfunction "39_39") (pintype "passive"))
      (node (ref "SV2") (pin "40") (pinfunction "40_40") (pintype "passive"))
      (node (ref "SW1") (pin "2") (pinfunction "S_2") (pintype "passive"))
      (node (ref "SW1") (pin "3") (pinfunction "S_3") (pintype "passive"))
      (node (ref "SW2") (pin "2") (pinfunction "S_2") (pintype "passive"))
      (node (ref "SW2") (pin "3") (pinfunction "S_3") (pintype "passive"))
      (node (ref "SW3") (pin "2") (pinfunction "S_2") (pintype "passive"))
      (node (ref "SW3") (pin "3") (pinfunction "S_3") (pintype "passive"))
      (node (ref "SW4") (pin "2") (pinfunction "S_2") (pintype "passive"))
      (node (ref "SW4") (pin "3") (pinfunction "S_3") (pintype "passive"))
      (node (ref "X2") (pin "2") (pinfunction "GND_2") (pintype "power_in"))
      (node (ref "X2") (pin "4") (pinfunction "GND_4") (pintype "power_in"))
      (node (ref "X3") (pin "GND") (pinfunction "SHIELD_GND") (pintype "power_in"))
      (node (ref "X3") (pin "GND@1") (pinfunction "SHIELD_GND@1") (pintype "power_in"))
      (node (ref "X3") (pin "GND@2") (pinfunction "SHIELD_GND@2") (pintype "power_in"))
      (node (ref "X3") (pin "GND@3") (pinfunction "SHIELD_GND@3") (pintype "power_in"))
      (node (ref "X4") (pin "2") (pinfunction "GND_2") (pintype "power_in"))
      (node (ref "X4") (pin "4") (pinfunction "GND_4") (pintype "power_in"))
      (node (ref "X5") (pin "2") (pinfunction "2_2") (pintype "passive"))
    )
    (net (code "7") (name "I2C1_SCL") (class "Default")
      (node (ref "IC4") (pin "92") (pinfunction "PB6_92") (pintype "bidirectional"))
      (node (ref "IC6") (pin "2") (pinfunction "SCL_2") (pintype "bidirectional"))
    )
    (net (code "8") (name "I2C1_SDA") (class "Default")
      (node (ref "IC4") (pin "96") (pinfunction "PB9_96") (pintype "bidirectional"))
      (node (ref "IC6") (pin "1") (pinfunction "SDA_1") (pintype "bidirectional"))
    )
    (net (code "9") (name "I2S2_CK") (class "Default")
      (node (ref "IC4") (pin "47") (pinfunction "PB10_47") (pintype "bidirectional"))
      (node (ref "IC5") (pin "27") (pinfunction "DCLK_27") (pintype "bidirectional"))
    )
    (net (code "10") (name "I2S2_SD") (class "Default")
      (node (ref "IC4") (pin "18") (pinfunction "PC3_18") (pintype "bidirectional"))
      (node (ref "IC5") (pin "33") (pinfunction "DOUT_33") (pintype "output"))
    )
    (net (code "11") (name "I2S2_WS") (class "Default")
      (node (ref "IC4") (pin "51") (pinfunction "PB12_51") (pintype "bidirectional"))
      (node (ref "IC5") (pin "28") (pinfunction "DFS_28") (pintype "bidirectional"))
    )
    (net (code "12") (name "I2S3_CK") (class "Default")
      (node (ref "IC4") (pin "78") (pinfunction "PC10_78") (pintype "bidirectional"))
      (node (ref "IC6") (pin "38") (pinfunction "SCLK_38") (pintype "input"))
    )
    (net (code "13") (name "I2S3_MCK") (class "Default")
      (node (ref "IC4") (pin "64") (pinfunction "PC7_64") (pintype "bidirectional"))
      (node (ref "IC6") (pin "37") (pinfunction "MCLK_37") (pintype "input"))
    )
    (net (code "14") (name "I2S3_SD") (class "Default")
      (node (ref "IC4") (pin "80") (pinfunction "PC12_80") (pintype "bidirectional"))
      (node (ref "IC6") (pin "39") (pinfunction "SDIN_39") (pintype "input"))
    )
    (net (code "15") (name "I2S3_WS") (class "Default")
      (node (ref "IC4") (pin "29") (pinfunction "PA4_29") (pintype "bidirectional"))
      (node (ref "IC6") (pin "40") (pinfunction "LRCK_40") (pintype "input"))
    )
    (net (code "16") (name "NRST") (class "Default")
      (node (ref "C65") (pin "2") (pinfunction "2_2") (pintype "passive"))
      (node (ref "IC4") (pin "14") (pinfunction "NRST_14") (pintype "bidirectional"))
      (node (ref "J2") (pin "10") (pinfunction "RESET_10") (pintype "bidirectional"))
      (node (ref "R8") (pin "1") (pinfunction "1_1") (pintype "passive"))
      (node (ref "SW1") (pin "4") (pinfunction "P_4") (pintype "passive"))
    )
    (net (code "17") (name "Net-(C31-Pad2)") (class "Default")
      (node (ref "C31") (pin "2") (pinfunction "2_2") (pintype "passive"))
      (node (ref "L3") (pin "1") (pinfunction "1_1") (pintype "passive"))
    )
    (net (code "18") (name "Net-(C52-Pad1)") (class "Default")
      (node (ref "C52") (pin "1") (pinfunction "1_1") (pintype "passive"))
      (node (ref "R6") (pin "2") (pinfunction "2_2") (pintype "passive"))
    )
    (net (code "19") (name "Net-(C54-Pad1)") (class "Default")
      (node (ref "C54") (pin "1") (pinfunction "1_1") (pintype "passive"))
      (node (ref "R7") (pin "2") (pinfunction "2_2") (pintype "passive"))
    )
    (net (code "20") (name "Net-(C66-Pad2)") (class "Default")
      (node (ref "C66") (pin "2") (pinfunction "2_2") (pintype "passive"))
      (node (ref "R9") (pin "2") (pinfunction "2_2") (pintype "passive"))
      (node (ref "SW2") (pin "4") (pinfunction "P_4") (pintype "passive"))
    )
    (net (code "21") (name "Net-(C67-Pad2)") (class "Default")
      (node (ref "C67") (pin "2") (pinfunction "2_2") (pintype "passive"))
      (node (ref "R10") (pin "2") (pinfunction "2_2") (pintype "passive"))
      (node (ref "SW3") (pin "4") (pinfunction "P_4") (pintype "passive"))
    )
    (net (code "22") (name "Net-(C68-Pad2)") (class "Default")
      (node (ref "C68") (pin "2") (pinfunction "2_2") (pintype "passive"))
      (node (ref "R11") (pin "2") (pinfunction "2_2") (pintype "passive"))
      (node (ref "SW4") (pin "4") (pinfunction "P_4") (pintype "passive"))
    )
    (net (code "23") (name "Net-(CON1-D+)") (class "Default")
      (node (ref "CON1") (pin "3") (pinfunction "D+_3") (pintype "bidirectional"))
      (node (ref "R3") (pin "1") (pinfunction "1_1") (pintype "passive"))
    )
    (net (code "24") (name "Net-(CON1-D-)") (class "Default")
      (node (ref "CON1") (pin "2") (pinfunction "D-_2") (pintype "bidirectional"))
      (node (ref "R2") (pin "1") (pinfunction "1_1") (pintype "passive"))
    )
    (net (code "25") (name "Net-(CON1-VBUS)") (class "Default")
      (node (ref "CON1") (pin "1") (pinfunction "VBUS_1") (pintype "bidirectional"))
      (node (ref "F1") (pin "P$1") (pinfunction "P$1_P$1") (pintype "bidirectional"))
      (node (ref "J1") (pin "2") (pinfunction "2_2") (pintype "passive"))
    )
    (net (code "26") (name "Net-(D1-C)") (class "Default")
      (node (ref "C31") (pin "1") (pinfunction "1_1") (pintype "passive"))
      (node (ref "D1") (pin "K") (pinfunction "C_K") (pintype "passive"))
      (node (ref "X3") (pin "PIN") (pinfunction "PIN_PIN") (pintype "passive"))
    )
    (net (code "27") (name "Net-(F1-PadP$2)") (class "Default")
      (node (ref "F1") (pin "P$2") (pinfunction "P$2_P$2") (pintype "bidirectional"))
      (node (ref "L1") (pin "1") (pinfunction "1_1") (pintype "passive"))
    )
    (net (code "28") (name "Net-(IC1-BYPASS)") (class "Default")
      (node (ref "C7") (pin "1") (pinfunction "1_1") (pintype "passive"))
      (node (ref "IC1") (pin "4") (pinfunction "BYPASS_4") (pintype "power_in"))
    )
    (net (code "29") (name "Net-(IC2-BYPASS)") (class "Default")
      (node (ref "C8") (pin "1") (pinfunction "1_1") (pintype "passive"))
      (node (ref "IC2") (pin "4") (pinfunction "BYPASS_4") (pintype "power_in"))
    )
    (net (code "30") (name "Net-(IC3-BYPASS)") (class "Default")
      (node (ref "C9") (pin "1") (pinfunction "1_1") (pintype "passive"))
      (node (ref "IC3") (pin "4") (pinfunction "BYPASS_4") (pintype "power_in"))
    )
    (net (code "31") (name "Net-(IC4-BOOT0)") (class "Default")
      (node (ref "IC4") (pin "94") (pinfunction "BOOT0_94") (pintype "input"))
      (node (ref "R4") (pin "1") (pinfunction "1_1") (pintype "passive"))
    )
    (net (code "32") (name "Net-(IC4-PH0)") (class "Default")
      (node (ref "C17") (pin "1") (pinfunction "1_1") (pintype "passive"))
      (node (ref "IC4") (pin "12") (pinfunction "PH0_12") (pintype "bidirectional"))
      (node (ref "X2") (pin "3") (pinfunction "3_3") (pintype "passive"))
    )
    (net (code "33") (name "Net-(IC4-PH1)") (class "Default")
      (node (ref "C18") (pin "1") (pinfunction "1_1") (pintype "passive"))
      (node (ref "IC4") (pin "13") (pinfunction "PH1_13") (pintype "bidirectional"))
      (node (ref "X2") (pin "1") (pinfunction "1_1") (pintype "passive"))
    )
    (net (code "34") (name "Net-(IC4-VCAP_1)") (class "Default")
      (node (ref "C22") (pin "1") (pinfunction "1_1") (pintype "passive"))
      (node (ref "IC4") (pin "49") (pinfunction "VCAP_1_49") (pintype "power_in"))
    )
    (net (code "35") (name "Net-(IC4-VCAP_2)") (class "Default")
      (node (ref "C28") (pin "1") (pinfunction "1_1") (pintype "passive"))
      (node (ref "IC4") (pin "73") (pinfunction "VCAP_2_73") (pintype "power_in"))
    )
    (net (code "36") (name "Net-(IC4-VDDA)") (class "Default")
      (node (ref "C19") (pin "1") (pinfunction "1_1") (pintype "passive"))
      (node (ref "C20") (pin "1") (pinfunction "1_1") (pintype "passive"))
      (node (ref "C21") (pin "1") (pinfunction "1_1") (pintype "passive"))
      (node (ref "IC4") (pin "21") (pinfunction "VREF+_21") (pintype "power_in"))
      (node (ref "IC4") (pin "22") (pinfunction "VDDA_22") (pintype "power_in"))
      (node (ref "L2") (pin "2") (pinfunction "2_2") (pintype "passive"))
    )
    (net (code "37") (name "Net-(IC5-ABYP)") (class "Default")
      (node (ref "C34") (pin "2") (pinfunction "2_2") (pintype "passive"))
      (node (ref "C35") (pin "2") (pinfunction "2_2") (pintype "passive"))
      (node (ref "C36") (pin "2") (pinfunction "2_2") (pintype "passive"))
      (node (ref "IC5") (pin "13") (pinfunction "ABYP_13") (pintype "power_in"))
    )
    (net (code "38") (name "Net-(IC5-DACREF)") (class "Default")
      (node (ref "C38") (pin "1") (pinfunction "1_1") (pintype "passive"))
      (node (ref "IC5") (pin "17") (pinfunction "DACREF_17") (pintype "power_in"))
    )
    (net (code "39") (name "Net-(IC5-DBYP)") (class "Default")
      (node (ref "C42") (pin "2") (pinfunction "2_2") (pintype "passive"))
      (node (ref "C43") (pin "2") (pinfunction "2_2") (pintype "passive"))
      (node (ref "C44") (pin "2") (pinfunction "2_2") (pintype "passive"))
      (node (ref "C45") (pin "2") (pinfunction "2_2") (pintype "passive"))
      (node (ref "C46") (pin "2") (pinfunction "2_2") (pintype "passive"))
      (node (ref "C47") (pin "2") (pinfunction "2_2") (pintype "passive"))
      (node (ref "C48") (pin "2") (pinfunction "2_2") (pintype "passive"))
      (node (ref "C49") (pin "2") (pinfunction "2_2") (pintype "passive"))
      (node (ref "C50") (pin "2") (pinfunction "2_2") (pintype "passive"))
      (node (ref "IC5") (pin "36") (pinfunction "DBYP_36") (pintype "power_in"))
    )
    (net (code "40") (name "Net-(IC5-LOUT)") (class "Default")
      (node (ref "C39") (pin "1") (pinfunction "1_1") (pintype "passive"))
      (node (ref "IC5") (pin "18") (pinfunction "LOUT_18") (pintype "output"))
      (node (ref "TP2") (pin "P$1") (pinfunction "TP_P$1") (pintype "passive"))
    )
    (net (code "41") (name "Net-(IC5-ROUT)") (class "Default")
      (node (ref "C40") (pin "1") (pinfunction "1_1") (pintype "passive"))
      (node (ref "IC5") (pin "19") (pinfunction "ROUT_19") (pintype "output"))
      (node (ref "TP1") (pin "P$1") (pinfunction "TP_P$1") (pintype "passive"))
    )
    (net (code "42") (name "Net-(IC5-VHFI)") (class "Default")
      (node (ref "C32") (pin "2") (pinfunction "2_2") (pintype "passive"))
      (node (ref "IC5") (pin "10") (pinfunction "VHFI_10") (pintype "input"))
      (node (ref "L3") (pin "2") (pinfunction "2_2") (pintype "passive"))
      (node (ref "L4") (pin "2") (pinfunction "2_2") (pintype "passive"))
      (node (ref "L5") (pin "2") (pinfunction "2_2") (pintype "passive"))
    )
    (net (code "43") (name "Net-(IC5-VHFSW)") (class "Default")
      (node (ref "IC5") (pin "11") (pinfunction "VHFSW_11") (pintype "output"))
      (node (ref "L5") (pin "1") (pinfunction "1_1") (pintype "passive"))
    )
    (net (code "44") (name "Net-(IC5-XTALI)") (class "Default")
      (node (ref "C37") (pin "2") (pinfunction "2_2") (pintype "passive"))
      (node (ref "IC5") (pin "15") (pinfunction "XTALI_15") (pintype "input"))
      (node (ref "X4") (pin "1") (pinfunction "1_1") (pintype "passive"))
    )
    (net (code "45") (name "Net-(IC5-XTALO)") (class "Default")
      (node (ref "C41") (pin "2") (pinfunction "2_2") (pintype "passive"))
      (node (ref "IC5") (pin "16") (pinfunction "XTALO_16") (pintype "output"))
      (node (ref "X4") (pin "3") (pinfunction "3_3") (pintype "passive"))
    )
    (net (code "46") (name "Net-(IC6--VHPFILT)") (class "Default")
      (node (ref "C51") (pin "1") (pinfunction "1_1") (pintype "passive"))
      (node (ref "IC6") (pin "10") (pinfunction "-VHPFILT_10") (pintype "power_in"))
    )
    (net (code "47") (name "Net-(IC6-AFILTA)") (class "Default")
      (node (ref "C60") (pin "2") (pinfunction "2_2") (pintype "passive"))
      (node (ref "IC6") (pin "27") (pinfunction "AFILTA_27") (pintype "power_in"))
    )
    (net (code "48") (name "Net-(IC6-AFILTB)") (class "Default")
      (node (ref "C58") (pin "2") (pinfunction "2_2") (pintype "passive"))
      (node (ref "IC6") (pin "28") (pinfunction "AFILTB_28") (pintype "power_in"))
    )
    (net (code "49") (name "Net-(IC6-FILT+)") (class "Default")
      (node (ref "C55") (pin "2") (pinfunction "2_2") (pintype "passive"))
      (node (ref "IC6") (pin "18") (pinfunction "FILT+_18") (pintype "power_in"))
    )
    (net (code "50") (name "Net-(IC6-FLYN)") (class "Default")
      (node (ref "C53") (pin "1") (pinfunction "1_1") (pintype "passive"))
      (node (ref "IC6") (pin "11") (pinfunction "FLYN_11") (pintype "power_in"))
    )
    (net (code "51") (name "Net-(IC6-FLYP)") (class "Default")
      (node (ref "C53") (pin "2") (pinfunction "2_2") (pintype "passive"))
      (node (ref "IC6") (pin "12") (pinfunction "FLYP_12") (pintype "power_in"))
    )
    (net (code "52") (name "Net-(IC6-HP{slash}LINE_OUTA)") (class "Default")
      (node (ref "C54") (pin "2") (pinfunction "2_2") (pintype "passive"))
      (node (ref "IC6") (pin "15") (pinfunction "HP/LINE_OUTA_15") (pintype "output"))
      (node (ref "X5") (pin "1") (pinfunction "1_1") (pintype "passive"))
    )
    (net (code "53") (name "Net-(IC6-HP{slash}LINE_OUTB)") (class "Default")
      (node (ref "C52") (pin "2") (pinfunction "2_2") (pintype "passive"))
      (node (ref "IC6") (pin "14") (pinfunction "HP/LINE_OUTB_14") (pintype "output"))
      (node (ref "X5") (pin "3") (pinfunction "3_3") (pintype "passive"))
    )
    (net (code "54") (name "Net-(IC6-SPKR_OUTA+)") (class "Default")
      (node (ref "IC6") (pin "4") (pinfunction "SPKR_OUTA+_4") (pintype "output"))
      (node (ref "J3") (pin "1") (pinfunction "1_1") (pintype "passive"))
    )
    (net (code "55") (name "Net-(IC6-SPKR_OUTA-)") (class "Default")
      (node (ref "IC6") (pin "6") (pinfunction "SPKR_OUTA-_6") (pintype "output"))
      (node (ref "J3") (pin "2") (pinfunction "2_2") (pintype "passive"))
    )
    (net (code "56") (name "Net-(IC6-SPKR_OUTB+)") (class "Default")
      (node (ref "IC6") (pin "7") (pinfunction "SPKR_OUTB+_7") (pintype "output"))
      (node (ref "J4") (pin "1") (pinfunction "1_1") (pintype "passive"))
    )
    (net (code "57") (name "Net-(IC6-SPKR_OUTB-)") (class "Default")
      (node (ref "IC6") (pin "9") (pinfunction "SPKR_OUTB-_9") (pintype "output"))
      (node (ref "J4") (pin "2") (pinfunction "2_2") (pintype "passive"))
    )
    (net (code "58") (name "Net-(IC6-VQ)") (class "Default")
      (node (ref "C56") (pin "2") (pinfunction "2_2") (pintype "passive"))
      (node (ref "IC6") (pin "19") (pinfunction "VQ_19") (pintype "power_in"))
    )
    (net (code "59") (name "Net-(LED1-PadA)") (class "Default")
      (node (ref "LED1") (pin "A") (pinfunction "A_A") (pintype "passive"))
      (node (ref "R12") (pin "2") (pinfunction "2_2") (pintype "passive"))
    )
    (net (code "60") (name "Net-(LED2-PadA)") (class "Default")
      (node (ref "LED2") (pin "A") (pinfunction "A_A") (pintype "passive"))
      (node (ref "R13") (pin "2") (pinfunction "2_2") (pintype "passive"))
    )
    (net (code "61") (name "Net-(LED3-PadA)") (class "Default")
      (node (ref "LED3") (pin "A") (pinfunction "A_A") (pintype "passive"))
      (node (ref "R14") (pin "2") (pinfunction "2_2") (pintype "passive"))
    )
    (net (code "62") (name "Net-(LED4-PadA)") (class "Default")
      (node (ref "LED4") (pin "A") (pinfunction "A_A") (pintype "passive"))
      (node (ref "R15") (pin "2") (pinfunction "2_2") (pintype "passive"))
    )
    (net (code "63") (name "PA0") (class "Default")
      (node (ref "IC4") (pin "23") (pinfunction "PA0_23") (pintype "bidirectional"))
      (node (ref "SV1") (pin "13") (pinfunction "13_13") (pintype "passive"))
    )
    (net (code "64") (name "PA1") (class "Default")
      (node (ref "IC4") (pin "24") (pinfunction "PA1_24") (pintype "bidirectional"))
      (node (ref "SV1") (pin "14") (pinfunction "14_14") (pintype "passive"))
    )
    (net (code "65") (name "PA2") (class "Default")
      (node (ref "IC4") (pin "25") (pinfunction "PA2_25") (pintype "bidirectional"))
      (node (ref "SV1") (pin "15") (pinfunction "15_15") (pintype "passive"))
    )
    (net (code "66") (name "PA3") (class "Default")
      (node (ref "IC4") (pin "26") (pinfunction "PA3_26") (pintype "bidirectional"))
      (node (ref "SV1") (pin "16") (pinfunction "16_16") (pintype "passive"))
    )
    (net (code "67") (name "PA8") (class "Default")
      (node (ref "IC4") (pin "67") (pinfunction "PA8_67") (pintype "bidirectional"))
      (node (ref "SV2") (pin "15") (pinfunction "15_15") (pintype "passive"))
    )
    (net (code "68") (name "PA9") (class "Default")
      (node (ref "IC4") (pin "68") (pinfunction "PA9_68") (pintype "bidirectional"))
      (node (ref "R1") (pin "1") (pinfunction "1_1") (pintype "passive"))
      (node (ref "SV2") (pin "16") (pinfunction "16_16") (pintype "passive"))
    )
    (net (code "69") (name "PA10") (class "Default")
      (node (ref "CON1") (pin "4") (pinfunction "ID_4") (pintype "bidirectional"))
      (node (ref "IC4") (pin "69") (pinfunction "PA10_69") (pintype "bidirectional"))
      (node (ref "SV2") (pin "17") (pinfunction "17_17") (pintype "passive"))
    )
    (net (code "70") (name "PB0") (class "Default")
      (node (ref "IC4") (pin "35") (pinfunction "PB0_35") (pintype "bidirectional"))
      (node (ref "SV1") (pin "23") (pinfunction "23_23") (pintype "passive"))
    )
    (net (code "71") (name "PB1") (class "Default")
      (node (ref "IC4") (pin "36") (pinfunction "PB1_36") (pintype "bidirectional"))
      (node (ref "SV1") (pin "24") (pinfunction "24_24") (pintype "passive"))
    )
    (net (code "72") (name "PB2") (class "Default")
      (node (ref "IC4") (pin "37") (pinfunction "PB2_37") (pintype "bidirectional"))
      (node (ref "R5") (pin "1") (pinfunction "1_1") (pintype "passive"))
      (node (ref "SV1") (pin "25") (pinfunction "25_25") (pintype "passive"))
    )
    (net (code "73") (name "PB4") (class "Default")
      (node (ref "IC4") (pin "90") (pinfunction "PB4_90") (pintype "bidirectional"))
      (node (ref "SV2") (pin "26") (pinfunction "26_26") (pintype "passive"))
    )
    (net (code "74") (name "PB5") (class "Default")
      (node (ref "IC4") (pin "91") (pinfunction "PB5_91") (pintype "bidirectional"))
      (node (ref "SV2") (pin "27") (pinfunction "27_27") (pintype "passive"))
    )
    (net (code "75") (name "PB11") (class "Default")
      (node (ref "IC4") (pin "48") (pinfunction "PB11_48") (pintype "bidirectional"))
      (node (ref "R11") (pin "1") (pinfunction "1_1") (pintype "passive"))
      (node (ref "SV1") (pin "36") (pinfunction "36_36") (pintype "passive"))
    )
    (net (code "76") (name "PB13") (class "Default")
      (node (ref "IC4") (pin "52") (pinfunction "PB13_52") (pintype "bidirectional"))
      (node (ref "SV2") (pin "1") (pinfunction "1_1") (pintype "passive"))
    )
    (net (code "77") (name "PB14") (class "Default")
      (node (ref "IC4") (pin "53") (pinfunction "PB14_53") (pintype "bidirectional"))
      (node (ref "SV2") (pin "2") (pinfunction "2_2") (pintype "passive"))
    )
    (net (code "78") (name "PB15") (class "Default")
      (node (ref "IC4") (pin "54") (pinfunction "PB15_54") (pintype "bidirectional"))
      (node (ref "SV2") (pin "3") (pinfunction "3_3") (pintype "passive"))
    )
    (net (code "79") (name "PC0") (class "Default")
      (node (ref "IC4") (pin "15") (pinfunction "PC0_15") (pintype "bidirectional"))
      (node (ref "SV1") (pin "9") (pinfunction "9_9") (pintype "passive"))
    )
    (net (code "80") (name "PC1") (class "Default")
      (node (ref "IC4") (pin "16") (pinfunction "PC1_16") (pintype "bidirectional"))
      (node (ref "SV1") (pin "10") (pinfunction "10_10") (pintype "passive"))
    )
    (net (code "81") (name "PC2") (class "Default")
      (node (ref "IC4") (pin "17") (pinfunction "PC2_17") (pintype "bidirectional"))
      (node (ref "SV1") (pin "11") (pinfunction "11_11") (pintype "passive"))
    )
    (net (code "82") (name "PC4") (class "Default")
      (node (ref "IC4") (pin "33") (pinfunction "PC4_33") (pintype "bidirectional"))
      (node (ref "SV1") (pin "21") (pinfunction "21_21") (pintype "passive"))
    )
    (net (code "83") (name "PC5") (class "Default")
      (node (ref "IC4") (pin "34") (pinfunction "PC5_34") (pintype "bidirectional"))
      (node (ref "SV1") (pin "22") (pinfunction "22_22") (pintype "passive"))
    )
    (net (code "84") (name "PC6") (class "Default")
      (node (ref "IC4") (pin "63") (pinfunction "PC6_63") (pintype "bidirectional"))
      (node (ref "SV2") (pin "12") (pinfunction "12_12") (pintype "passive"))
    )
    (net (code "85") (name "PC8") (class "Default")
      (node (ref "IC4") (pin "65") (pinfunction "PC8_65") (pintype "bidirectional"))
      (node (ref "SV2") (pin "13") (pinfunction "13_13") (pintype "passive"))
    )
    (net (code "86") (name "PC9") (class "Default")
      (node (ref "IC4") (pin "66") (pinfunction "PC9_66") (pintype "bidirectional"))
      (node (ref "SV2") (pin "14") (pinfunction "14_14") (pintype "passive"))
    )
    (net (code "87") (name "PC11") (class "Default")
      (node (ref "IC4") (pin "79") (pinfunction "PC11_79") (pintype "bidirectional"))
      (node (ref "SV2") (pin "18") (pinfunction "18_18") (pintype "passive"))
    )
    (net (code "88") (name "PC13") (class "Default")
      (node (ref "IC4") (pin "7") (pinfunction "PC13_7") (pintype "bidirectional"))
      (node (ref "SV1") (pin "6") (pinfunction "6_6") (pintype "passive"))
    )
    (net (code "89") (name "PC14") (class "Default")
      (node (ref "IC4") (pin "8") (pinfunction "PC14_8") (pintype "bidirectional"))
      (node (ref "SV1") (pin "7") (pinfunction "7_7") (pintype "passive"))
    )
    (net (code "90") (name "PC15") (class "Default")
      (node (ref "IC4") (pin "9") (pinfunction "PC15_9") (pintype "bidirectional"))
      (node (ref "SV1") (pin "8") (pinfunction "8_8") (pintype "passive"))
    )
    (net (code "91") (name "PD0") (class "Default")
      (node (ref "IC4") (pin "81") (pinfunction "PD0_81") (pintype "bidirectional"))
      (node (ref "SV2") (pin "19") (pinfunction "19_19") (pintype "passive"))
    )
    (net (code "92") (name "PD1") (class "Default")
      (node (ref "IC4") (pin "82") (pinfunction "PD1_82") (pintype "bidirectional"))
      (node (ref "SV2") (pin "20") (pinfunction "20_20") (pintype "passive"))
    )
    (net (code "93") (name "PD2") (class "Default")
      (node (ref "IC4") (pin "83") (pinfunction "PD2_83") (pintype "bidirectional"))
      (node (ref "SV2") (pin "21") (pinfunction "21_21") (pintype "passive"))
    )
    (net (code "94") (name "PD3") (class "Default")
      (node (ref "IC4") (pin "84") (pinfunction "PD3_84") (pintype "bidirectional"))
      (node (ref "SV2") (pin "22") (pinfunction "22_22") (pintype "passive"))
    )
    (net (code "95") (name "PD5") (class "Default")
      (node (ref "IC4") (pin "86") (pinfunction "PD5_86") (pintype "bidirectional"))
      (node (ref "SV2") (pin "23") (pinfunction "23_23") (pintype "passive"))
    )
    (net (code "96") (name "PD6") (class "Default")
      (node (ref "IC4") (pin "87") (pinfunction "PD6_87") (pintype "bidirectional"))
      (node (ref "SV2") (pin "24") (pinfunction "24_24") (pintype "passive"))
    )
    (net (code "97") (name "PD7") (class "Default")
      (node (ref "IC4") (pin "88") (pinfunction "PD7_88") (pintype "bidirectional"))
      (node (ref "SV2") (pin "25") (pinfunction "25_25") (pintype "passive"))
    )
    (net (code "98") (name "PD8") (class "Default")
      (node (ref "IC4") (pin "55") (pinfunction "PD8_55") (pintype "bidirectional"))
      (node (ref "SV2") (pin "4") (pinfunction "4_4") (pintype "passive"))
    )
    (net (code "99") (name "PD9") (class "Default")
      (node (ref "IC4") (pin "56") (pinfunction "PD9_56") (pintype "bidirectional"))
      (node (ref "SV2") (pin "5") (pinfunction "5_5") (pintype "passive"))
    )
    (net (code "100") (name "PD10") (class "Default")
      (node (ref "IC4") (pin "57") (pinfunction "PD10_57") (pintype "bidirectional"))
      (node (ref "SV2") (pin "6") (pinfunction "6_6") (pintype "passive"))
    )
    (net (code "101") (name "PD11") (class "Default")
      (node (ref "IC4") (pin "58") (pinfunction "PD11_58") (pintype "bidirectional"))
      (node (ref "SV2") (pin "7") (pinfunction "7_7") (pintype "passive"))
    )
    (net (code "102") (name "PD12") (class "Default")
      (node (ref "IC4") (pin "59") (pinfunction "PD12_59") (pintype "bidirectional"))
      (node (ref "SV2") (pin "8") (pinfunction "8_8") (pintype "passive"))
    )
    (net (code "103") (name "PD13") (class "Default")
      (node (ref "IC4") (pin "60") (pinfunction "PD13_60") (pintype "bidirectional"))
      (node (ref "SV2") (pin "9") (pinfunction "9_9") (pintype "passive"))
    )
    (net (code "104") (name "PD14") (class "Default")
      (node (ref "IC4") (pin "61") (pinfunction "PD14_61") (pintype "bidirectional"))
      (node (ref "SV2") (pin "10") (pinfunction "10_10") (pintype "passive"))
    )
    (net (code "105") (name "PD15") (class "Default")
      (node (ref "IC4") (pin "62") (pinfunction "PD15_62") (pintype "bidirectional"))
      (node (ref "SV2") (pin "11") (pinfunction "11_11") (pintype "passive"))
    )
    (net (code "106") (name "PE0") (class "Default")
      (node (ref "IC4") (pin "97") (pinfunction "PE0_97") (pintype "bidirectional"))
      (node (ref "SV2") (pin "28") (pinfunction "28_28") (pintype "passive"))
    )
    (net (code "107") (name "PE1") (class "Default")
      (node (ref "IC4") (pin "98") (pinfunction "PE1_98") (pintype "bidirectional"))
      (node (ref "SV2") (pin "29") (pinfunction "29_29") (pintype "passive"))
    )
    (net (code "108") (name "PE2") (class "Default")
      (node (ref "IC4") (pin "1") (pinfunction "PE2_1") (pintype "bidirectional"))
      (node (ref "R13") (pin "1") (pinfunction "1_1") (pintype "passive"))
      (node (ref "SV1") (pin "1") (pinfunction "1_1") (pintype "passive"))
    )
    (net (code "109") (name "PE3") (class "Default")
      (node (ref "IC4") (pin "2") (pinfunction "PE3_2") (pintype "bidirectional"))
      (node (ref "R14") (pin "1") (pinfunction "1_1") (pintype "passive"))
      (node (ref "SV1") (pin "2") (pinfunction "2_2") (pintype "passive"))
    )
    (net (code "110") (name "PE4") (class "Default")
      (node (ref "IC4") (pin "3") (pinfunction "PE4_3") (pintype "bidirectional"))
      (node (ref "R15") (pin "1") (pinfunction "1_1") (pintype "passive"))
      (node (ref "SV1") (pin "3") (pinfunction "3_3") (pintype "passive"))
    )
    (net (code "111") (name "PE5") (class "Default")
      (node (ref "IC4") (pin "4") (pinfunction "PE5_4") (pintype "bidirectional"))
      (node (ref "SV1") (pin "4") (pinfunction "4_4") (pintype "passive"))
    )
    (net (code "112") (name "PE6") (class "Default")
      (node (ref "IC4") (pin "5") (pinfunction "PE6_5") (pintype "bidirectional"))
      (node (ref "SV1") (pin "5") (pinfunction "5_5") (pintype "passive"))
    )
    (net (code "113") (name "PE7") (class "Default")
      (node (ref "IC4") (pin "38") (pinfunction "PE7_38") (pintype "bidirectional"))
      (node (ref "SV1") (pin "26") (pinfunction "26_26") (pintype "passive"))
    )
    (net (code "114") (name "PE8") (class "Default")
      (node (ref "IC4") (pin "39") (pinfunction "PE8_39") (pintype "bidirectional"))
      (node (ref "SV1") (pin "27") (pinfunction "27_27") (pintype "passive"))
    )
    (net (code "115") (name "PE9") (class "Default")
      (node (ref "IC4") (pin "40") (pinfunction "PE9_40") (pintype "bidirectional"))
      (node (ref "SV1") (pin "28") (pinfunction "28_28") (pintype "passive"))
    )
    (net (code "116") (name "PE10") (class "Default")
      (node (ref "IC4") (pin "41") (pinfunction "PE10_41") (pintype "bidirectional"))
      (node (ref "SV1") (pin "29") (pinfunction "29_29") (pintype "passive"))
    )
    (net (code "117") (name "PE11") (class "Default")
      (node (ref "IC4") (pin "42") (pinfunction "PE11_42") (pintype "bidirectional"))
      (node (ref "SV1") (pin "30") (pinfunction "30_30") (pintype "passive"))
    )
    (net (code "118") (name "PE12") (class "Default")
      (node (ref "IC4") (pin "43") (pinfunction "PE12_43") (pintype "bidirectional"))
      (node (ref "SV1") (pin "31") (pinfunction "31_31") (pintype "passive"))
    )
    (net (code "119") (name "PE13") (class "Default")
      (node (ref "IC4") (pin "44") (pinfunction "PE13_44") (pintype "bidirectional"))
      (node (ref "SV1") (pin "32") (pinfunction "32_32") (pintype "passive"))
    )
    (net (code "120") (name "PE14") (class "Default")
      (node (ref "IC4") (pin "45") (pinfunction "PE14_45") (pintype "bidirectional"))
      (node (ref "R9") (pin "1") (pinfunction "1_1") (pintype "passive"))
      (node (ref "SV1") (pin "33") (pinfunction "33_33") (pintype "passive"))
    )
    (net (code "121") (name "PE15") (class "Default")
      (node (ref "IC4") (pin "46") (pinfunction "PE15_46") (pintype "bidirectional"))
      (node (ref "R10") (pin "1") (pinfunction "1_1") (pintype "passive"))
      (node (ref "SV1") (pin "34") (pinfunction "34_34") (pintype "passive"))
    )
    (net (code "122") (name "SI4688_INTB") (class "Default")
      (node (ref "IC4") (pin "93") (pinfunction "PB7_93") (pintype "bidirectional"))
      (node (ref "IC5") (pin "3") (pinfunction "INTB_3") (pintype "output"))
      (node (ref "TP3") (pin "1") (pinfunction "TP_1") (pintype "passive"))
    )
    (net (code "123") (name "SI4688_RSTB") (class "Default")
      (node (ref "IC4") (pin "95") (pinfunction "PB8_95") (pintype "bidirectional"))
      (node (ref "IC5") (pin "4") (pinfunction "RSTB_4") (pintype "input"))
      (node (ref "TP4") (pin "1") (pinfunction "TP_1") (pintype "passive"))
    )
    (net (code "124") (name "SPI1_MISO") (class "Default")
      (node (ref "IC4") (pin "31") (pinfunction "PA6_31") (pintype "bidirectional"))
      (node (ref "IC5") (pin "32") (pinfunction "MISO_32") (pintype "bidirectional"))
    )
    (net (code "125") (name "SPI1_MOSI") (class "Default")
      (node (ref "IC4") (pin "32") (pinfunction "PA7_32") (pintype "bidirectional"))
      (node (ref "IC5") (pin "31") (pinfunction "MOSI_31") (pintype "bidirectional"))
    )
    (net (code "126") (name "SPI1_NSS") (class "Default")
      (node (ref "IC4") (pin "77") (pinfunction "PA15_77") (pintype "bidirectional"))
      (node (ref "IC5") (pin "29") (pinfunction "SSB_29") (pintype "input"))
    )
    (net (code "127") (name "SPI1_SCK") (class "Default")
      (node (ref "IC4") (pin "30") (pinfunction "PA5_30") (pintype "bidirectional"))
      (node (ref "IC5") (pin "30") (pinfunction "SCLK_30") (pintype "input"))
    )
    (net (code "128") (name "SWCLK") (class "Default")
      (node (ref "IC4") (pin "76") (pinfunction "PA14_76") (pintype "bidirectional"))
      (node (ref "J2") (pin "4") (pinfunction "SWCLK_4") (pintype "output"))
    )
    (net (code "129") (name "SWDIO") (class "Default")
      (node (ref "IC4") (pin "72") (pinfunction "PA13_72") (pintype "bidirectional"))
      (node (ref "J2") (pin "2") (pinfunction "SWDIO_2") (pintype "bidirectional"))
    )
    (net (code "130") (name "SWO") (class "Default")
      (node (ref "IC4") (pin "89") (pinfunction "PB3_89") (pintype "bidirectional"))
      (node (ref "J2") (pin "6") (pinfunction "SWO_6") (pintype "output"))
    )
    (net (code "131") (name "USB_D_N") (class "Default")
      (node (ref "IC4") (pin "70") (pinfunction "PA11_70") (pintype "bidirectional"))
      (node (ref "R2") (pin "2") (pinfunction "2_2") (pintype "passive"))
    )
    (net (code "132") (name "USB_D_P") (class "Default")
      (node (ref "IC4") (pin "71") (pinfunction "PA12_71") (pintype "bidirectional"))
      (node (ref "R3") (pin "2") (pinfunction "2_2") (pintype "passive"))
    )
    (net (code "133") (name "unconnected-(IC5-NC-Pad14)") (class "Default")
      (node (ref "IC5") (pin "14") (pinfunction "NC_14") (pintype "no_connect"))
    )
    (net (code "134") (name "unconnected-(IC5-NC-Pad20)") (class "Default")
      (node (ref "IC5") (pin "20") (pinfunction "NC_20") (pintype "no_connect"))
    )
    (net (code "135") (name "unconnected-(IC5-NC-Pad21)") (class "Default")
      (node (ref "IC5") (pin "21") (pinfunction "NC_21") (pintype "no_connect"))
    )
    (net (code "136") (name "unconnected-(IC5-NC-Pad22)") (class "Default")
      (node (ref "IC5") (pin "22") (pinfunction "NC_22") (pintype "no_connect"))
    )
    (net (code "137") (name "unconnected-(IC5-NC-Pad23)") (class "Default")
      (node (ref "IC5") (pin "23") (pinfunction "NC_23") (pintype "no_connect"))
    )
    (net (code "138") (name "unconnected-(IC5-NC-Pad24)") (class "Default")
      (node (ref "IC5") (pin "24") (pinfunction "NC_24") (pintype "no_connect"))
    )
    (net (code "139") (name "unconnected-(IC5-NC-Pad25)") (class "Default")
      (node (ref "IC5") (pin "25") (pinfunction "NC_25") (pintype "no_connect"))
    )
    (net (code "140") (name "unconnected-(IC5-NC-Pad26)") (class "Default")
      (node (ref "IC5") (pin "26") (pinfunction "NC_26") (pintype "no_connect"))
    )
    (net (code "141") (name "unconnected-(IC5-NC-Pad38)") (class "Default")
      (node (ref "IC5") (pin "38") (pinfunction "NC_38") (pintype "no_connect"))
    )
    (net (code "142") (name "unconnected-(IC5-NC-Pad43)") (class "Default")
      (node (ref "IC5") (pin "43") (pinfunction "NC_43") (pintype "no_connect"))
    )
    (net (code "143") (name "unconnected-(IC5-NC-Pad44)") (class "Default")
      (node (ref "IC5") (pin "44") (pinfunction "NC_44") (pintype "no_connect"))
    )
    (net (code "144") (name "unconnected-(IC5-NC-Pad45)") (class "Default")
      (node (ref "IC5") (pin "45") (pinfunction "NC_45") (pintype "no_connect"))
    )
    (net (code "145") (name "unconnected-(IC5-NC-Pad46)") (class "Default")
      (node (ref "IC5") (pin "46") (pinfunction "NC_46") (pintype "no_connect"))
    )
    (net (code "146") (name "unconnected-(IC5-NVMOSI-Pad48)") (class "Default")
      (node (ref "IC5") (pin "48") (pinfunction "NVMOSI_48") (pintype "output"))
    )
    (net (code "147") (name "unconnected-(IC5-NVSCLK-Pad2)") (class "Default")
      (node (ref "IC5") (pin "2") (pinfunction "NVSCLK_2") (pintype "output"))
    )
    (net (code "148") (name "unconnected-(IC5-NVSSB-Pad1)") (class "Default")
      (node (ref "IC5") (pin "1") (pinfunction "NVSSB_1") (pintype "output"))
    )
    (net (code "149") (name "unconnected-(IC6-AIN1A-Pad29)") (class "Default")
      (node (ref "IC6") (pin "29") (pinfunction "AIN1A_29") (pintype "input"))
    )
    (net (code "150") (name "unconnected-(IC6-AIN1B-Pad30)") (class "Default")
      (node (ref "IC6") (pin "30") (pinfunction "AIN1B_30") (pintype "input"))
    )
    (net (code "151") (name "unconnected-(IC6-AIN2A-Pad25)") (class "Default")
      (node (ref "IC6") (pin "25") (pinfunction "AIN2A_25") (pintype "input"))
    )
    (net (code "152") (name "unconnected-(IC6-AIN2B-Pad26)") (class "Default")
      (node (ref "IC6") (pin "26") (pinfunction "AIN2B_26") (pintype "input"))
    )
    (net (code "153") (name "unconnected-(IC6-AIN3A-Pad23)") (class "Default")
      (node (ref "IC6") (pin "23") (pinfunction "AIN3A_23") (pintype "input"))
    )
    (net (code "154") (name "unconnected-(IC6-AIN3B-Pad24)") (class "Default")
      (node (ref "IC6") (pin "24") (pinfunction "AIN3B_24") (pintype "input"))
    )
    (net (code "155") (name "unconnected-(IC6-AIN4A-Pad21)") (class "Default")
      (node (ref "IC6") (pin "21") (pinfunction "AIN4A_21") (pintype "input"))
    )
    (net (code "156") (name "unconnected-(IC6-AIN4B-Pad22)") (class "Default")
      (node (ref "IC6") (pin "22") (pinfunction "AIN4B_22") (pintype "input"))
    )
    (net (code "157") (name "unconnected-(IC6-TSTO1-Pad20)") (class "Default")
      (node (ref "IC6") (pin "20") (pinfunction "TSTO1_20") (pintype "no_connect"))
    )
    (net (code "158") (name "unconnected-(IC6-TSTO2-Pad36)") (class "Default")
      (node (ref "IC6") (pin "36") (pinfunction "TSTO2_36") (pintype "no_connect"))
    )
    (net (code "159") (name "unconnected-(J2-Pad7)") (class "Default")
      (node (ref "J2") (pin "7") (pinfunction "7_7") (pintype "no_connect"))
    )
    (net (code "160") (name "unconnected-(J2-Pad8)") (class "Default")
      (node (ref "J2") (pin "8") (pinfunction "8_8") (pintype "no_connect"))
    )
    (net (code "161") (name "unconnected-(J2-Pad9)") (class "Default")
      (node (ref "J2") (pin "9") (pinfunction "9_9") (pintype "no_connect"))
    )
    (net (code "162") (name "unconnected-(SV1-Pad12)") (class "Default")
      (node (ref "SV1") (pin "12") (pinfunction "12_12") (pintype "passive"))
    )
    (net (code "163") (name "unconnected-(SV2-Pad30)") (class "Default")
      (node (ref "SV2") (pin "30") (pinfunction "30_30") (pintype "passive"))
    )
    (net (code "164") (name "unconnected-(SW1-P-Pad1)") (class "Default")
      (node (ref "SW1") (pin "1") (pinfunction "P_1") (pintype "passive"))
    )
    (net (code "165") (name "unconnected-(SW2-P-Pad1)") (class "Default")
      (node (ref "SW2") (pin "1") (pinfunction "P_1") (pintype "passive"))
    )
    (net (code "166") (name "unconnected-(SW3-P-Pad1)") (class "Default")
      (node (ref "SW3") (pin "1") (pinfunction "P_1") (pintype "passive"))
    )
    (net (code "167") (name "unconnected-(SW4-P-Pad1)") (class "Default")
      (node (ref "SW4") (pin "1") (pinfunction "P_1") (pintype "passive"))
    )
    (net (code "168") (name "unconnected-(X5-2-Pad2@2)") (class "Default")
      (node (ref "X5") (pin "2@2") (pinfunction "2_2@2") (pintype "passive"))
    )
  )
)
